# 1.net
KiCad netlist of a schematic drawn in EAGLE
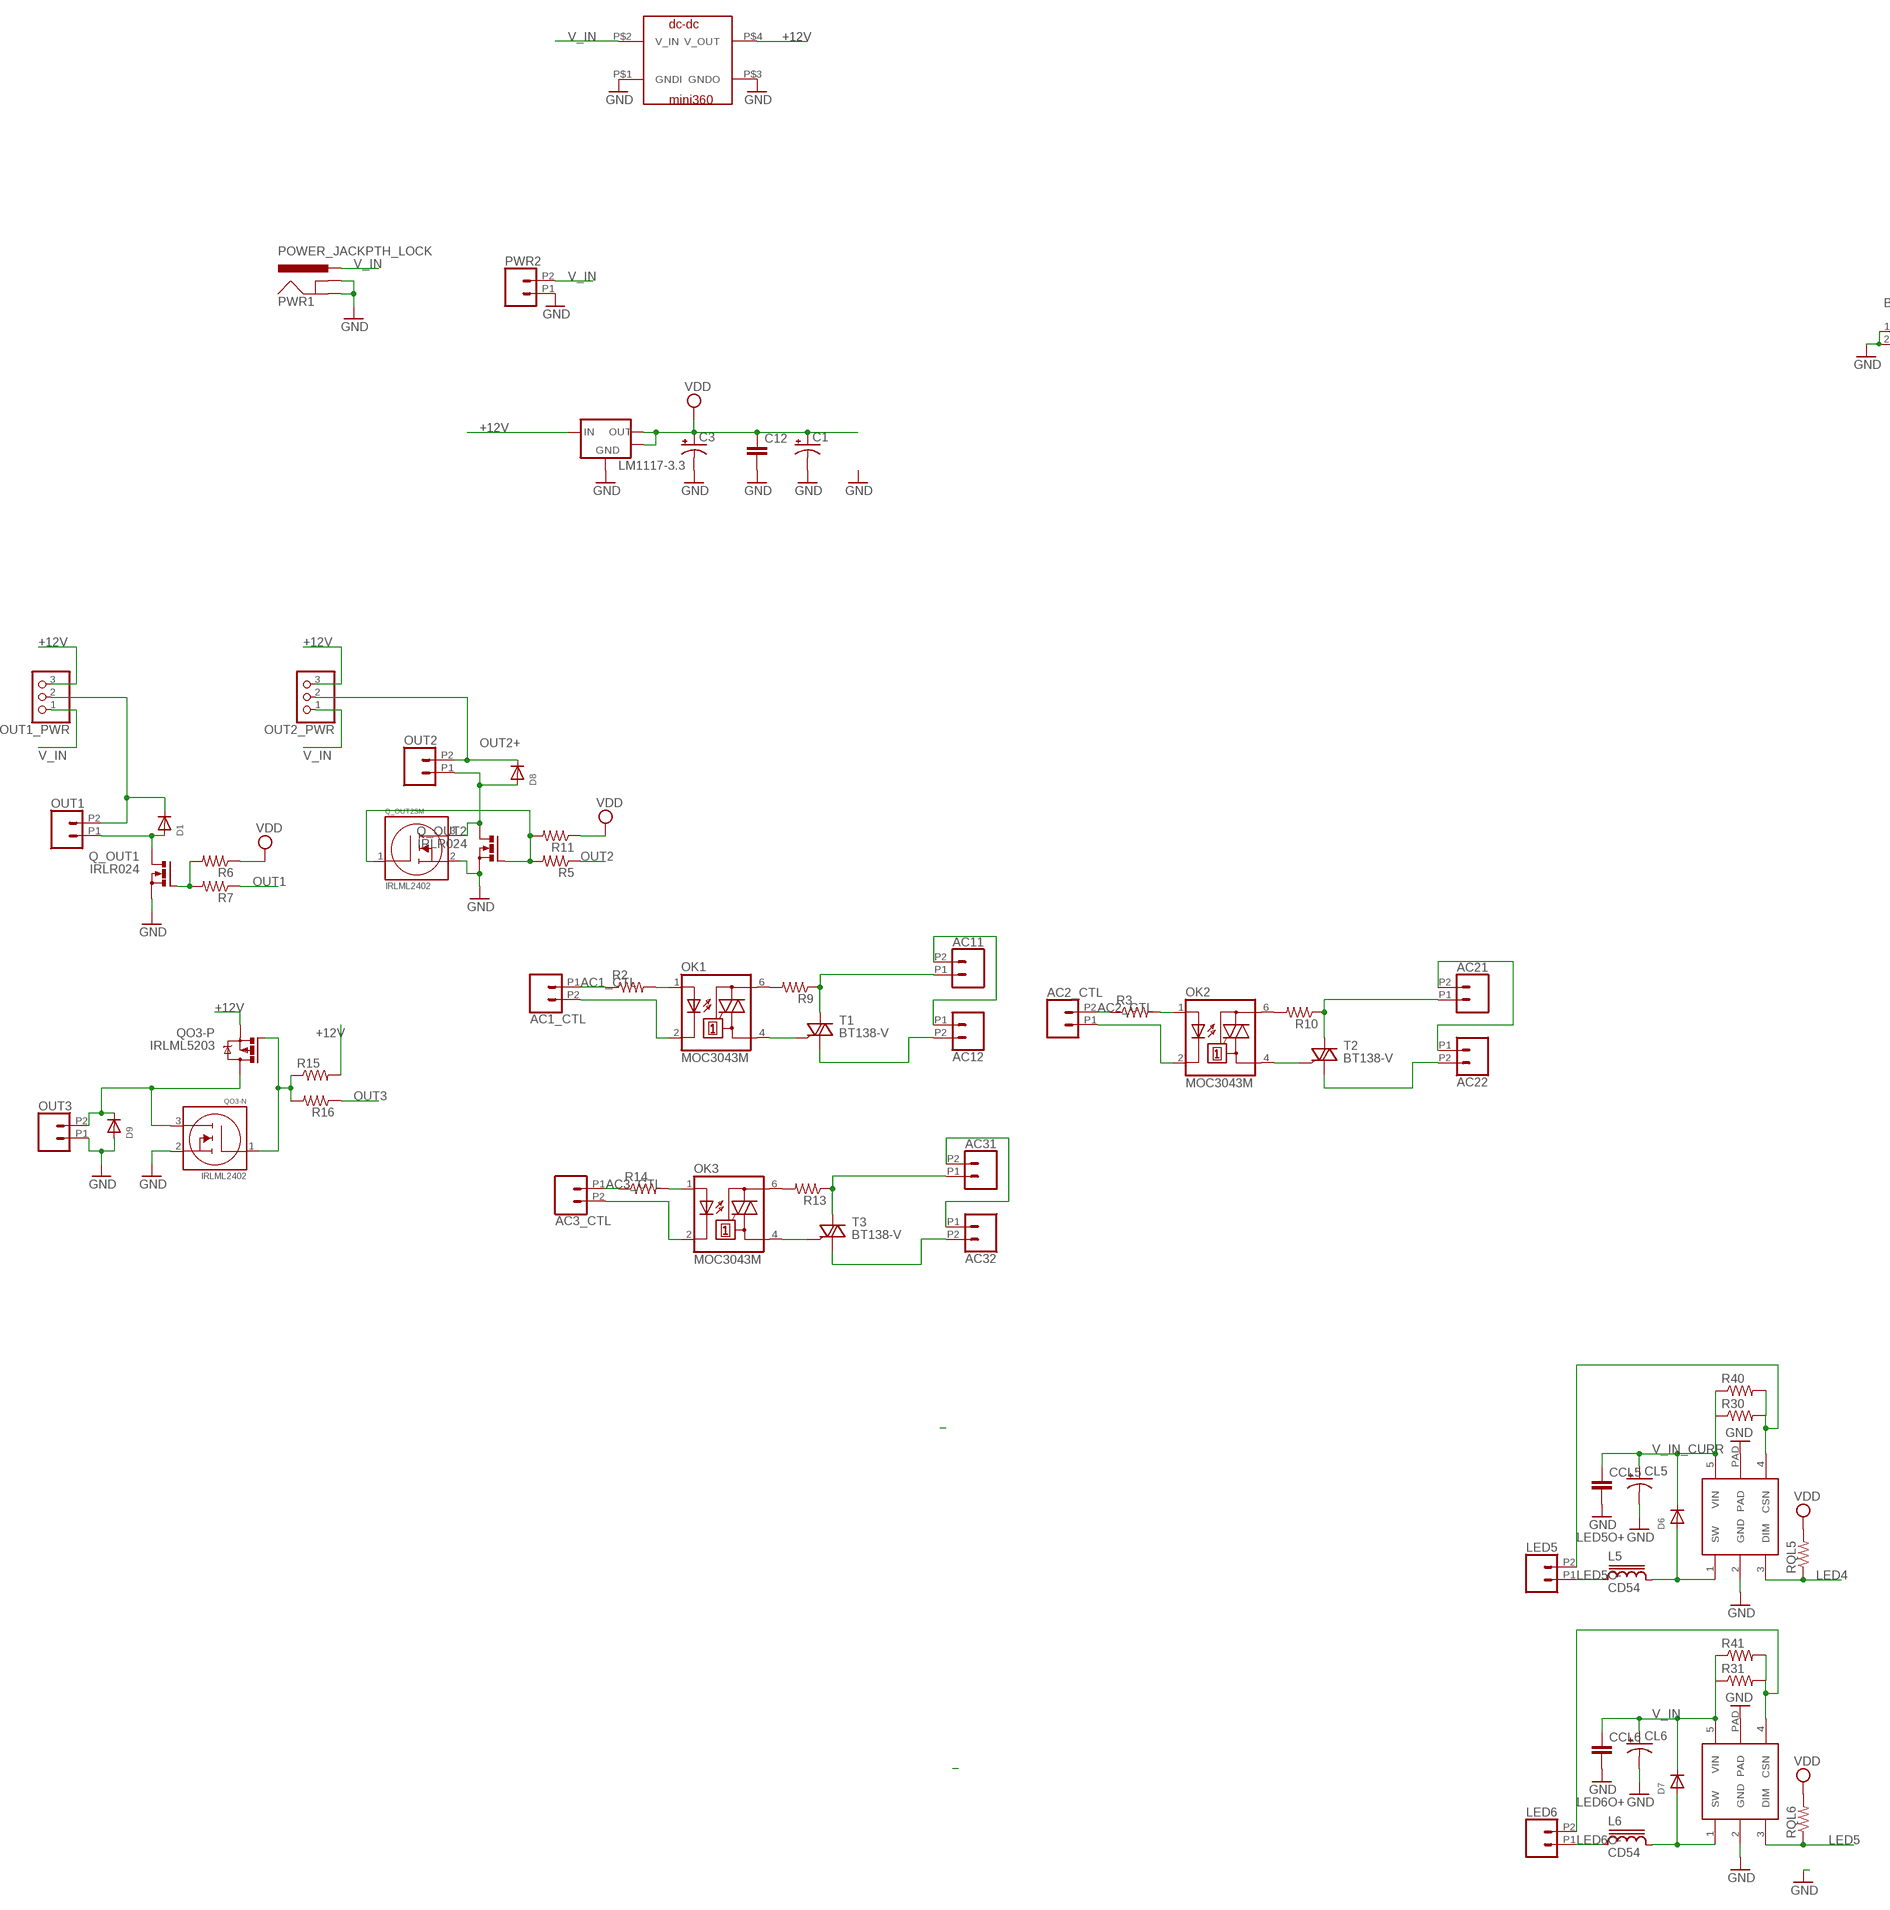
[diagram p0: schematic, sheet 1, part 1 of 3]
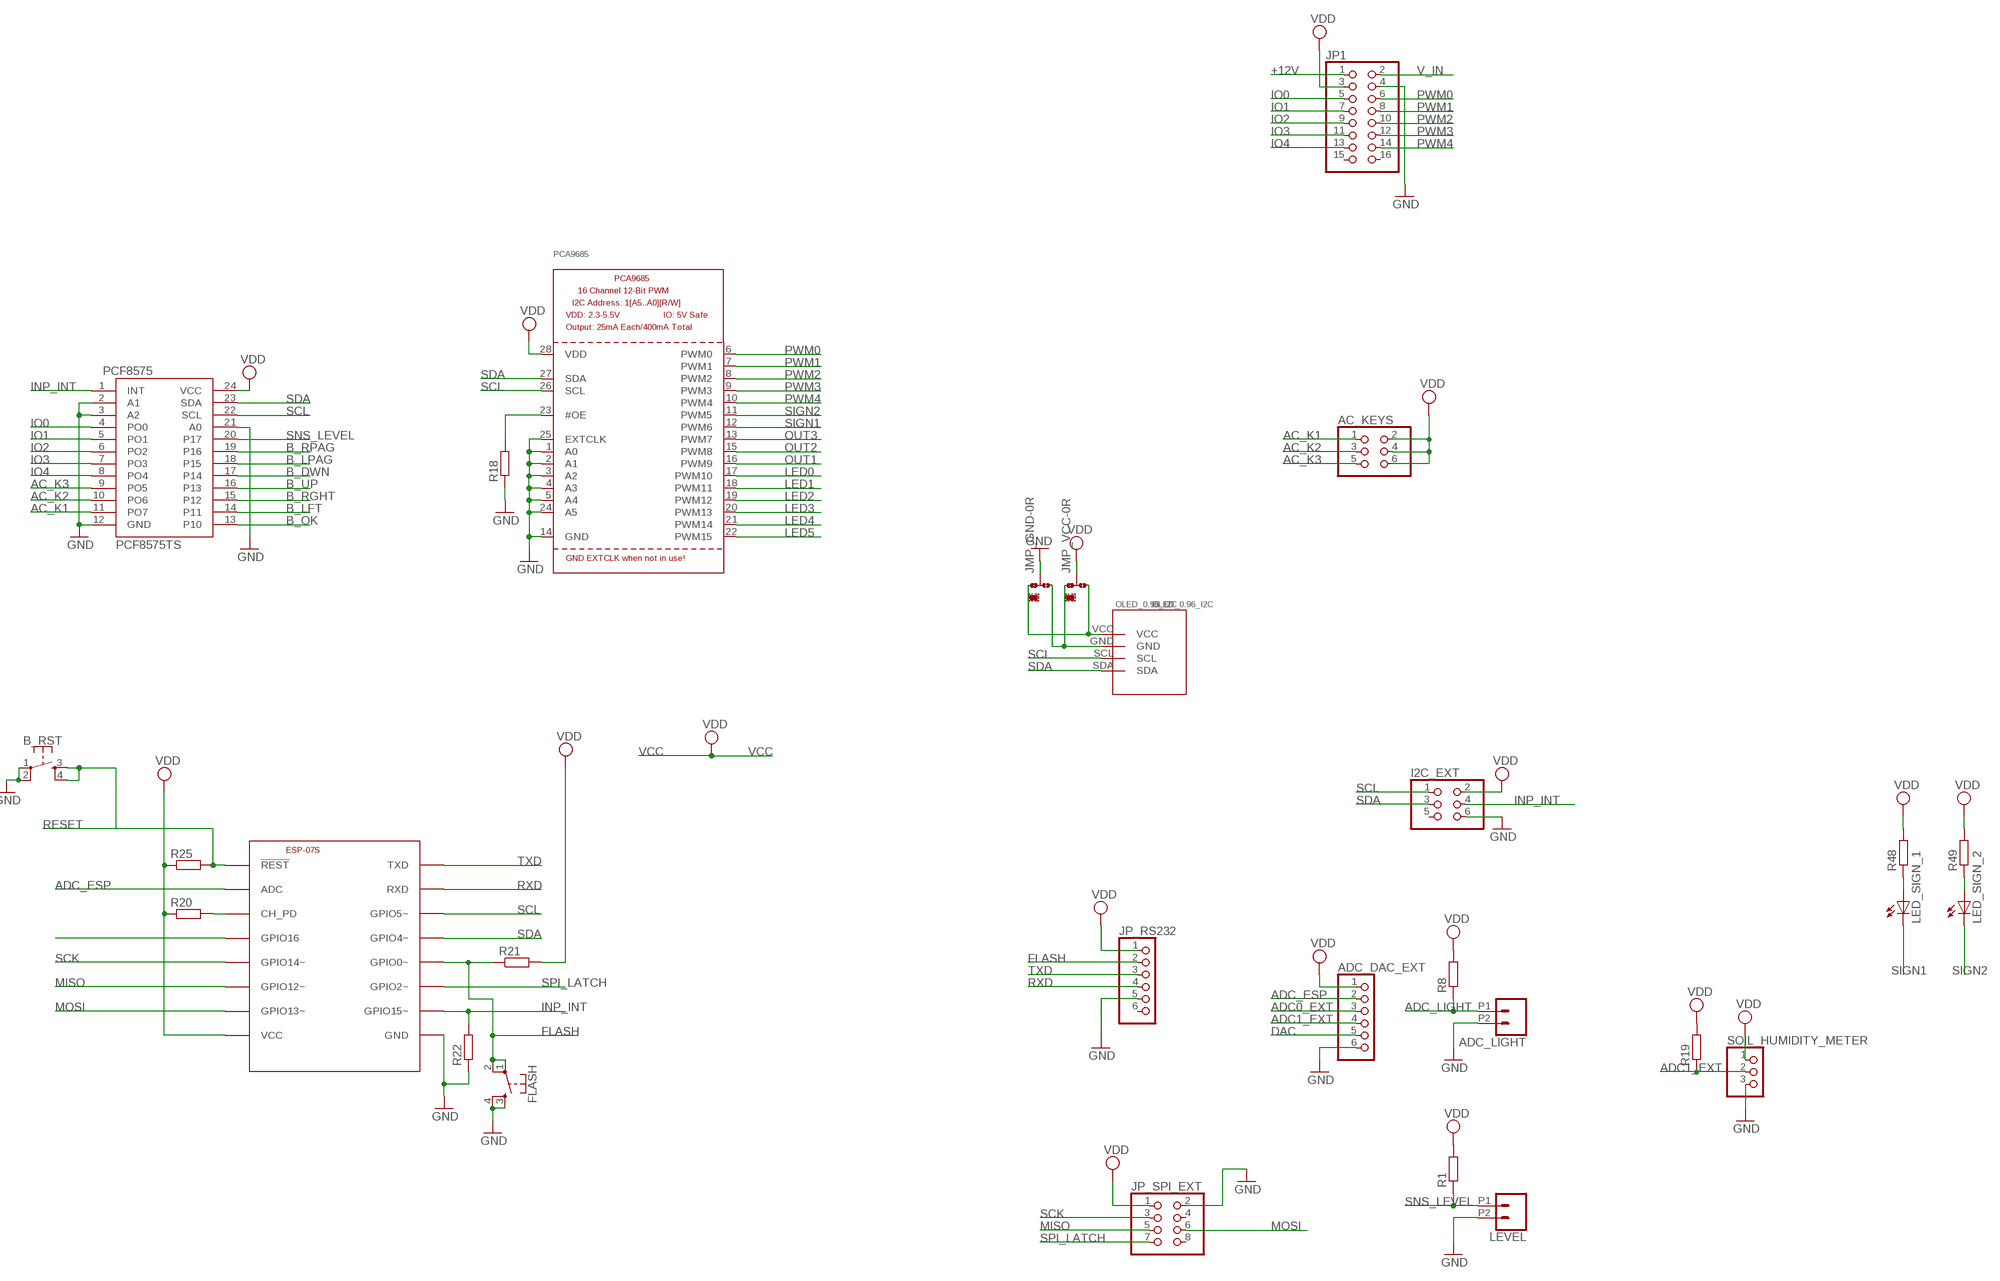
[diagram p1: schematic, sheet 1, part 2 of 3]
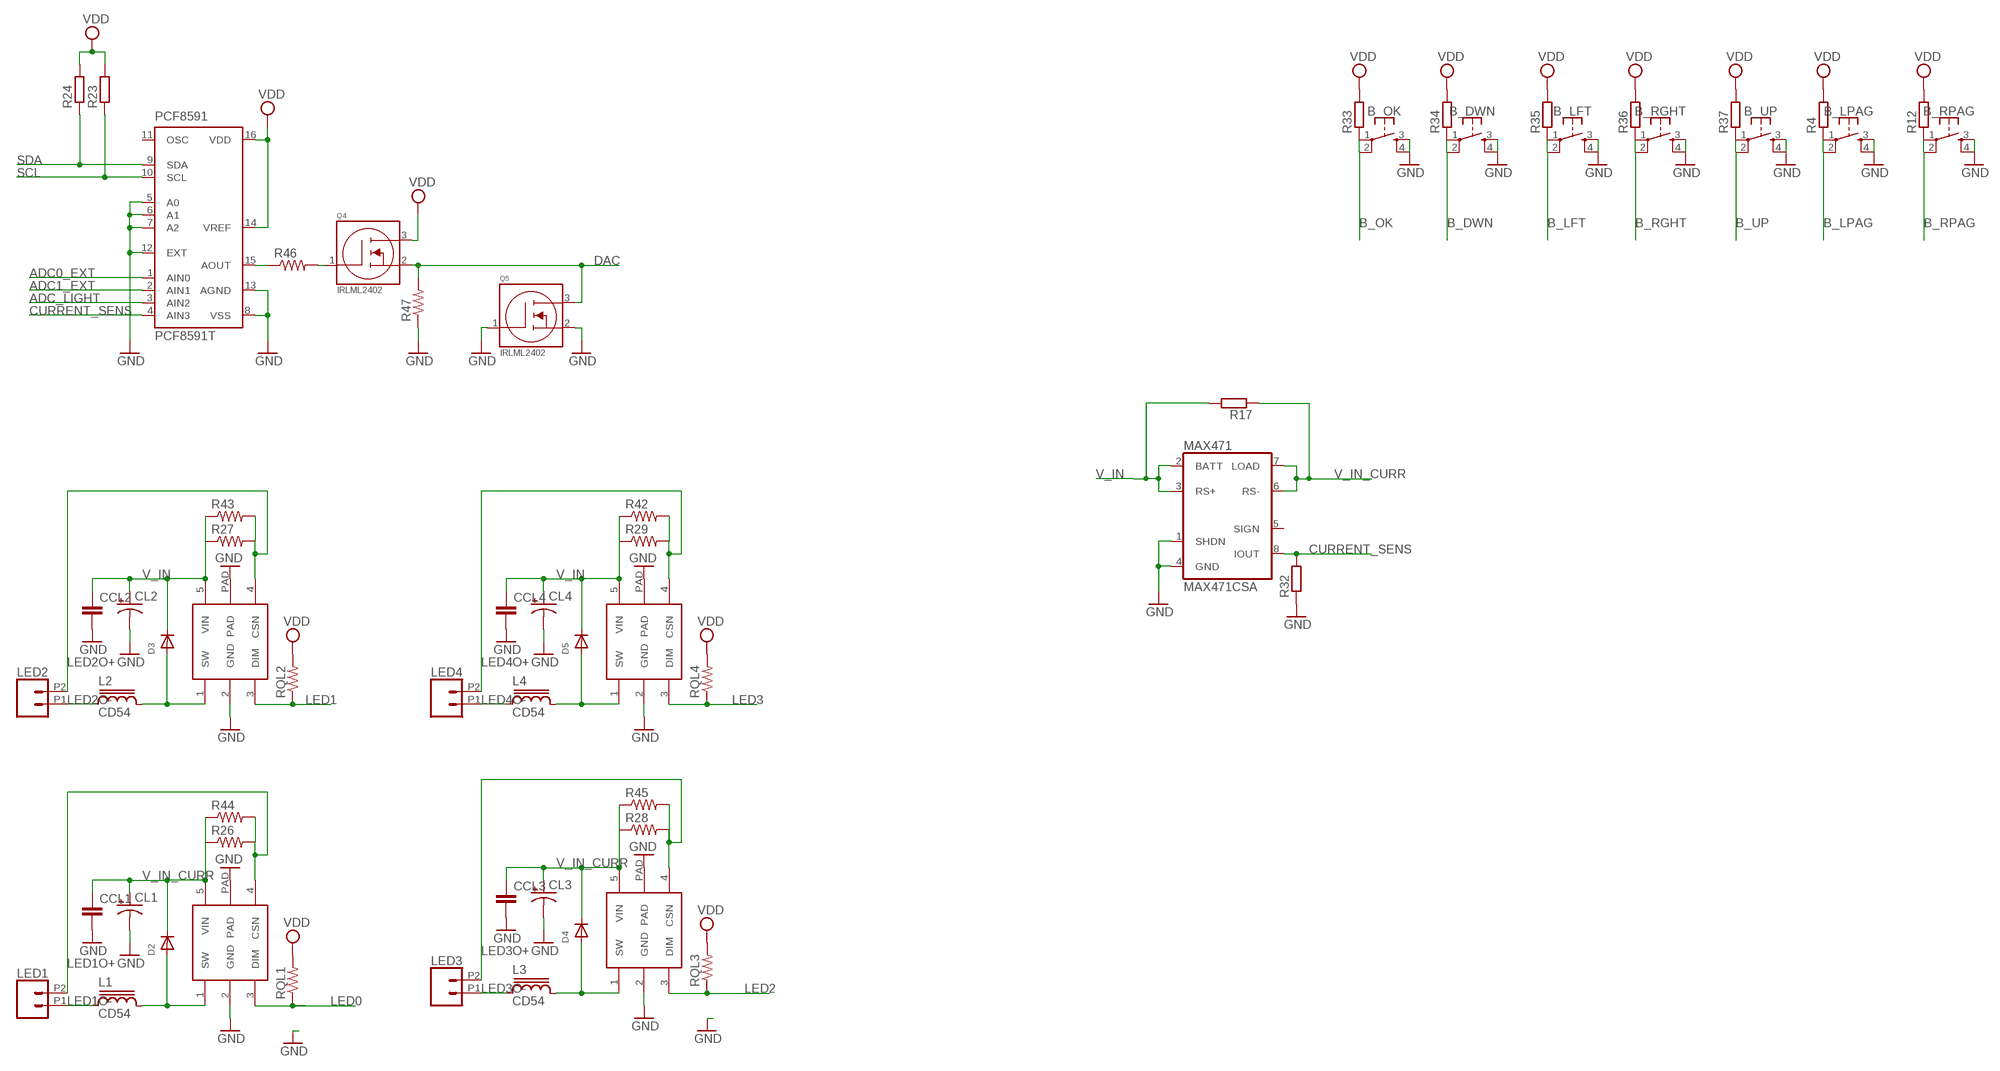
[diagram p2: schematic, sheet 1, part 3 of 3]

(export (version "E")
  (design (tool "Eeschema 10.0.6"))
  (components
    (comp (ref "AC1_CTL")
      (value "CONN_022.54MM_SCREWTERM")
      (footprint "eagle-import:1X02_2.54_SCREWTERM")
      (libsource (lib "eagle-import") (part "SparkFun-Retired_CONN_022.54MM_SCREWTERM"))
    )
    (comp (ref "AC2_CTL")
      (value "CONN_022.54MM_SCREWTERM")
      (footprint "eagle-import:1X02_2.54_SCREWTERM")
      (libsource (lib "eagle-import") (part "SparkFun-Retired_CONN_022.54MM_SCREWTERM"))
    )
    (comp (ref "AC3_CTL")
      (value "CONN_022.54MM_SCREWTERM")
      (footprint "eagle-import:1X02_2.54_SCREWTERM")
      (libsource (lib "eagle-import") (part "SparkFun-Retired_CONN_022.54MM_SCREWTERM"))
    )
    (comp (ref "AC11")
      (value "CONN_022.54MM_SCREWTERM")
      (footprint "eagle-import:1X02_2.54_SCREWTERM")
      (libsource (lib "eagle-import") (part "SparkFun-Retired_CONN_022.54MM_SCREWTERM"))
    )
    (comp (ref "AC12")
      (value "CONN_022.54MM_SCREWTERM")
      (footprint "eagle-import:1X02_2.54_SCREWTERM")
      (libsource (lib "eagle-import") (part "SparkFun-Retired_CONN_022.54MM_SCREWTERM"))
    )
    (comp (ref "AC21")
      (value "CONN_022.54MM_SCREWTERM")
      (footprint "eagle-import:1X02_2.54_SCREWTERM")
      (libsource (lib "eagle-import") (part "SparkFun-Retired_CONN_022.54MM_SCREWTERM"))
    )
    (comp (ref "AC22")
      (value "CONN_022.54MM_SCREWTERM")
      (footprint "eagle-import:1X02_2.54_SCREWTERM")
      (libsource (lib "eagle-import") (part "SparkFun-Retired_CONN_022.54MM_SCREWTERM"))
    )
    (comp (ref "AC31")
      (value "CONN_022.54MM_SCREWTERM")
      (footprint "eagle-import:1X02_2.54_SCREWTERM")
      (libsource (lib "eagle-import") (part "SparkFun-Retired_CONN_022.54MM_SCREWTERM"))
    )
    (comp (ref "AC32")
      (value "CONN_022.54MM_SCREWTERM")
      (footprint "eagle-import:1X02_2.54_SCREWTERM")
      (libsource (lib "eagle-import") (part "SparkFun-Retired_CONN_022.54MM_SCREWTERM"))
    )
    (comp (ref "AC_KEYS")
      (value "PINHD-2X3")
      (footprint "eagle-import:2X03")
      (libsource (lib "eagle-import") (part "PINHD-2X3"))
    )
    (comp (ref "ADC_DAC_EXT")
      (value "PINHD-1X6")
      (footprint "eagle-import:1X06")
      (libsource (lib "eagle-import") (part "PINHD-1X6"))
    )
    (comp (ref "ADC_LIGHT")
      (value "CONN_022.54MM_SCREWTERM")
      (footprint "eagle-import:1X02_2.54_SCREWTERM")
      (libsource (lib "eagle-import") (part "CONN_022.54MM_SCREWTERM"))
    )
    (comp (ref "B_DWN")
      (value "MOMENTARY-SWITCH-SPST-2-SMD-5.2MM")
      (footprint "eagle-import:TACTILE_SWITCH_SMD_5.2MM")
      (libsource (lib "eagle-import") (part "MOMENTARY-SWITCH-SPST-2-SMD-5.2MM"))
    )
    (comp (ref "B_LFT")
      (value "MOMENTARY-SWITCH-SPST-2-SMD-5.2MM")
      (footprint "eagle-import:TACTILE_SWITCH_SMD_5.2MM")
      (libsource (lib "eagle-import") (part "MOMENTARY-SWITCH-SPST-2-SMD-5.2MM"))
    )
    (comp (ref "B_LPAG")
      (value "MOMENTARY-SWITCH-SPST-2-SMD-5.2MM")
      (footprint "eagle-import:TACTILE_SWITCH_SMD_5.2MM")
      (libsource (lib "eagle-import") (part "MOMENTARY-SWITCH-SPST-2-SMD-5.2MM"))
    )
    (comp (ref "B_OK")
      (value "MOMENTARY-SWITCH-SPST-2-SMD-5.2MM")
      (footprint "eagle-import:TACTILE_SWITCH_SMD_5.2MM")
      (libsource (lib "eagle-import") (part "MOMENTARY-SWITCH-SPST-2-SMD-5.2MM"))
    )
    (comp (ref "B_RGHT")
      (value "MOMENTARY-SWITCH-SPST-2-SMD-5.2MM")
      (footprint "eagle-import:TACTILE_SWITCH_SMD_5.2MM")
      (libsource (lib "eagle-import") (part "MOMENTARY-SWITCH-SPST-2-SMD-5.2MM"))
    )
    (comp (ref "B_RPAG")
      (value "MOMENTARY-SWITCH-SPST-2-SMD-5.2MM")
      (footprint "eagle-import:TACTILE_SWITCH_SMD_5.2MM")
      (libsource (lib "eagle-import") (part "MOMENTARY-SWITCH-SPST-2-SMD-5.2MM"))
    )
    (comp (ref "B_RST")
      (value "MOMENTARY-SWITCH-SPST-2-SMD-5.2MM")
      (footprint "eagle-import:TACTILE_SWITCH_SMD_5.2MM")
      (libsource (lib "eagle-import") (part "MOMENTARY-SWITCH-SPST-2-SMD-5.2MM"))
    )
    (comp (ref "B_UP")
      (value "MOMENTARY-SWITCH-SPST-2-SMD-5.2MM")
      (footprint "eagle-import:TACTILE_SWITCH_SMD_5.2MM")
      (libsource (lib "eagle-import") (part "MOMENTARY-SWITCH-SPST-2-SMD-5.2MM"))
    )
    (comp (ref "C1")
      (value "CPOL-US153CLV-0505")
      (footprint "eagle-import:153CLV-0505")
      (libsource (lib "eagle-import") (part "CPOL-US153CLV-0505"))
    )
    (comp (ref "C3")
      (value "CPOL-US153CLV-0505")
      (footprint "eagle-import:153CLV-0505")
      (libsource (lib "eagle-import") (part "CPOL-US153CLV-0505"))
    )
    (comp (ref "C12")
      (value "C-EUC0805")
      (footprint "eagle-import:C0805")
      (libsource (lib "eagle-import") (part "C-EUC0805"))
    )
    (comp (ref "CCL1")
      (value "C-EUC0805K")
      (footprint "eagle-import:C0805K")
      (libsource (lib "eagle-import") (part "C-EUC0805K"))
    )
    (comp (ref "CCL2")
      (value "C-EUC0805K")
      (footprint "eagle-import:C0805K")
      (libsource (lib "eagle-import") (part "C-EUC0805K"))
    )
    (comp (ref "CCL3")
      (value "C-EUC0805K")
      (footprint "eagle-import:C0805K")
      (libsource (lib "eagle-import") (part "C-EUC0805K"))
    )
    (comp (ref "CCL4")
      (value "C-EUC0805K")
      (footprint "eagle-import:C0805K")
      (libsource (lib "eagle-import") (part "C-EUC0805K"))
    )
    (comp (ref "CCL5")
      (value "C-EUC0805K")
      (footprint "eagle-import:C0805K")
      (libsource (lib "eagle-import") (part "C-EUC0805K"))
    )
    (comp (ref "CCL6")
      (value "C-EUC0805K")
      (footprint "eagle-import:C0805K")
      (libsource (lib "eagle-import") (part "C-EUC0805K"))
    )
    (comp (ref "CL1")
      (value "CPOL-US153CLV-0605")
      (footprint "eagle-import:153CLV-0605")
      (libsource (lib "eagle-import") (part "CPOL-US153CLV-0605"))
    )
    (comp (ref "CL2")
      (value "CPOL-US153CLV-0605")
      (footprint "eagle-import:153CLV-0605")
      (libsource (lib "eagle-import") (part "CPOL-US153CLV-0605"))
    )
    (comp (ref "CL3")
      (value "CPOL-US153CLV-0605")
      (footprint "eagle-import:153CLV-0605")
      (libsource (lib "eagle-import") (part "CPOL-US153CLV-0605"))
    )
    (comp (ref "CL4")
      (value "CPOL-US153CLV-0605")
      (footprint "eagle-import:153CLV-0605")
      (libsource (lib "eagle-import") (part "CPOL-US153CLV-0605"))
    )
    (comp (ref "CL5")
      (value "CPOL-US153CLV-0605")
      (footprint "eagle-import:153CLV-0605")
      (libsource (lib "eagle-import") (part "CPOL-US153CLV-0605"))
    )
    (comp (ref "CL6")
      (value "CPOL-US153CLV-0605")
      (footprint "eagle-import:153CLV-0605")
      (libsource (lib "eagle-import") (part "CPOL-US153CLV-0605"))
    )
    (comp (ref "D1")
      (value "DIODESMA")
      (footprint "eagle-import:SMADIODE")
      (libsource (lib "eagle-import") (part "DIODESMA"))
    )
    (comp (ref "D2")
      (value "DIODESMA")
      (footprint "eagle-import:SMADIODE")
      (libsource (lib "eagle-import") (part "DIODESMA"))
    )
    (comp (ref "D3")
      (value "DIODESMA")
      (footprint "eagle-import:SMADIODE")
      (libsource (lib "eagle-import") (part "DIODESMA"))
    )
    (comp (ref "D4")
      (value "DIODESMA")
      (footprint "eagle-import:SMADIODE")
      (libsource (lib "eagle-import") (part "DIODESMA"))
    )
    (comp (ref "D5")
      (value "DIODESMA")
      (footprint "eagle-import:SMADIODE")
      (libsource (lib "eagle-import") (part "DIODESMA"))
    )
    (comp (ref "D6")
      (value "DIODESMA")
      (footprint "eagle-import:SMADIODE")
      (libsource (lib "eagle-import") (part "DIODESMA"))
    )
    (comp (ref "D7")
      (value "DIODESMA")
      (footprint "eagle-import:SMADIODE")
      (libsource (lib "eagle-import") (part "DIODESMA"))
    )
    (comp (ref "D8")
      (value "DIODESMA")
      (footprint "eagle-import:SMADIODE")
      (libsource (lib "eagle-import") (part "DIODESMA"))
    )
    (comp (ref "D9")
      (value "DIODESMA")
      (footprint "eagle-import:SMADIODE")
      (libsource (lib "eagle-import") (part "DIODESMA"))
    )
    (comp (ref "ESP-07S")
      (value "ESP8266-08")
      (footprint "eagle-import:ESP-08")
      (libsource (lib "eagle-import") (part "ESP8266-08"))
    )
    (comp (ref "FLASH")
      (value "MOMENTARY-SWITCH-SPST-2-SMD-5.2MM")
      (footprint "eagle-import:TACTILE_SWITCH_SMD_5.2MM")
      (libsource (lib "eagle-import") (part "MOMENTARY-SWITCH-SPST-2-SMD-5.2MM"))
    )
    (comp (ref "I2C_EXT")
      (value "PINHD-2X3")
      (footprint "eagle-import:2X03")
      (libsource (lib "eagle-import") (part "PINHD-2X3"))
    )
    (comp (ref "JMP_GND")
      (value "0R-JUMPA")
      (footprint "eagle-import:A0R-JMP")
      (libsource (lib "eagle-import") (part "0R-JUMPA"))
    )
    (comp (ref "JMP_VCC")
      (value "0R-JUMPA")
      (footprint "eagle-import:A0R-JMP")
      (libsource (lib "eagle-import") (part "0R-JUMPA"))
    )
    (comp (ref "JP1")
      (value "PINHD-2X8")
      (footprint "eagle-import:2X08")
      (libsource (lib "eagle-import") (part "PINHD-2X8"))
    )
    (comp (ref "JP_RS232")
      (value "PINHD-1X6")
      (footprint "eagle-import:1X06")
      (libsource (lib "eagle-import") (part "PINHD-1X6"))
    )
    (comp (ref "JP_SPI_EXT")
      (value "PINHD-2X4")
      (footprint "eagle-import:2X04")
      (libsource (lib "eagle-import") (part "PINHD-2X4"))
    )
    (comp (ref "L1")
      (value "CD54")
      (footprint "eagle-import:CD54")
      (libsource (lib "eagle-import") (part "CD54"))
    )
    (comp (ref "L2")
      (value "CD54")
      (footprint "eagle-import:CD54")
      (libsource (lib "eagle-import") (part "CD54"))
    )
    (comp (ref "L3")
      (value "CD54")
      (footprint "eagle-import:CD54")
      (libsource (lib "eagle-import") (part "CD54"))
    )
    (comp (ref "L4")
      (value "CD54")
      (footprint "eagle-import:CD54")
      (libsource (lib "eagle-import") (part "CD54"))
    )
    (comp (ref "L5")
      (value "CD54")
      (footprint "eagle-import:CD54")
      (libsource (lib "eagle-import") (part "CD54"))
    )
    (comp (ref "L6")
      (value "CD54")
      (footprint "eagle-import:CD54")
      (libsource (lib "eagle-import") (part "CD54"))
    )
    (comp (ref "LED1")
      (value "CONN_022.54MM_SCREWTERM")
      (footprint "eagle-import:1X02_2.54_SCREWTERM")
      (libsource (lib "eagle-import") (part "CONN_022.54MM_SCREWTERM"))
    )
    (comp (ref "LED2")
      (value "CONN_022.54MM_SCREWTERM")
      (footprint "eagle-import:1X02_2.54_SCREWTERM")
      (libsource (lib "eagle-import") (part "CONN_022.54MM_SCREWTERM"))
    )
    (comp (ref "LED3")
      (value "CONN_022.54MM_SCREWTERM")
      (footprint "eagle-import:1X02_2.54_SCREWTERM")
      (libsource (lib "eagle-import") (part "CONN_022.54MM_SCREWTERM"))
    )
    (comp (ref "LED4")
      (value "CONN_022.54MM_SCREWTERM")
      (footprint "eagle-import:1X02_2.54_SCREWTERM")
      (libsource (lib "eagle-import") (part "CONN_022.54MM_SCREWTERM"))
    )
    (comp (ref "LED5")
      (value "CONN_022.54MM_SCREWTERM")
      (footprint "eagle-import:1X02_2.54_SCREWTERM")
      (libsource (lib "eagle-import") (part "CONN_022.54MM_SCREWTERM"))
    )
    (comp (ref "LED6")
      (value "CONN_022.54MM_SCREWTERM")
      (footprint "eagle-import:1X02_2.54_SCREWTERM")
      (libsource (lib "eagle-import") (part "CONN_022.54MM_SCREWTERM"))
    )
    (comp (ref "LED_SIGN_1")
      (value "LEDCHIP-LED0805")
      (footprint "eagle-import:CHIP-LED0805")
      (libsource (lib "eagle-import") (part "LEDCHIP-LED0805"))
    )
    (comp (ref "LED_SIGN_2")
      (value "LEDCHIP-LED0805")
      (footprint "eagle-import:CHIP-LED0805")
      (libsource (lib "eagle-import") (part "LEDCHIP-LED0805"))
    )
    (comp (ref "LEVEL")
      (value "CONN_022.54MM_SCREWTERM")
      (footprint "eagle-import:1X02_2.54_SCREWTERM")
      (libsource (lib "eagle-import") (part "CONN_022.54MM_SCREWTERM"))
    )
    (comp (ref "LM1117-3.3")
      (value "LM1117-3.3")
      (footprint "eagle-import:SOT223")
      (libsource (lib "eagle-import") (part "LM1117-3.3"))
    )
    (comp (ref "MAX471")
      (value "MAX471CSA")
      (footprint "eagle-import:SO08")
      (libsource (lib "eagle-import") (part "MAX471CSA"))
    )
    (comp (ref "OK1")
      (value "MOC3043M")
      (footprint "eagle-import:DIL06")
      (fields (field (name "MF") "FAIRCHILD SEMICONDUCTOR") (field (name "MPN") "MOC3043-M"))
      (libsource (lib "eagle-import") (part "MOC3043M"))
    )
    (comp (ref "OK2")
      (value "MOC3043M")
      (footprint "eagle-import:DIL06")
      (fields (field (name "MF") "FAIRCHILD SEMICONDUCTOR") (field (name "MPN") "MOC3043-M"))
      (libsource (lib "eagle-import") (part "MOC3043M"))
    )
    (comp (ref "OK3")
      (value "MOC3043M")
      (footprint "eagle-import:DIL06")
      (fields (field (name "MF") "FAIRCHILD SEMICONDUCTOR") (field (name "MPN") "MOC3043-M"))
      (libsource (lib "eagle-import") (part "MOC3043M"))
    )
    (comp (ref "OLED_0.96_I2C")
      (value "OLED_0.96_I2C")
      (footprint "eagle-import:OLED_0.96_I2C")
      (libsource (lib "eagle-import") (part "OLED_0.96_I2C"))
    )
    (comp (ref "OUT1")
      (value "CONN_022.54MM_SCREWTERM")
      (footprint "eagle-import:1X02_2.54_SCREWTERM")
      (libsource (lib "eagle-import") (part "CONN_022.54MM_SCREWTERM"))
    )
    (comp (ref "OUT1_PWR")
      (value "PINHD-1X3")
      (footprint "eagle-import:1X03")
      (libsource (lib "eagle-import") (part "PINHD-1X3"))
    )
    (comp (ref "OUT2")
      (value "CONN_022.54MM_SCREWTERM")
      (footprint "eagle-import:1X02_2.54_SCREWTERM")
      (libsource (lib "eagle-import") (part "CONN_022.54MM_SCREWTERM"))
    )
    (comp (ref "OUT2_PWR")
      (value "PINHD-1X3")
      (footprint "eagle-import:1X03")
      (libsource (lib "eagle-import") (part "PINHD-1X3"))
    )
    (comp (ref "OUT3")
      (value "CONN_022.54MM_SCREWTERM")
      (footprint "eagle-import:1X02_2.54_SCREWTERM")
      (libsource (lib "eagle-import") (part "CONN_022.54MM_SCREWTERM"))
    )
    (comp (ref "PCA9685")
      (value "PCA9685")
      (footprint "eagle-import:TSSOP28")
      (libsource (lib "eagle-import") (part "PCA9685"))
    )
    (comp (ref "PCF8575")
      (value "PCF8575TS")
      (footprint "eagle-import:SSOP24")
      (libsource (lib "eagle-import") (part "PCF8575TS"))
    )
    (comp (ref "PCF8591")
      (value "PCF8591T")
      (footprint "eagle-import:SO16W")
      (fields (field (name "MPN") "PCF8591T/2,512"))
      (libsource (lib "eagle-import") (part "PCF8591T"))
    )
    (comp (ref "PWR1")
      (value "POWER_JACKPTH_LOCK")
      (footprint "eagle-import:POWER_JACK_PTH_LOCK")
      (libsource (lib "eagle-import") (part "POWER_JACKPTH_LOCK"))
    )
    (comp (ref "PWR2")
      (value "CONN_022.54MM_SCREWTERM")
      (footprint "eagle-import:1X02_2.54_SCREWTERM")
      (libsource (lib "eagle-import") (part "CONN_022.54MM_SCREWTERM"))
    )
    (comp (ref "Q4")
      (value "IRLML2402")
      (footprint "eagle-import:SOT23")
      (libsource (lib "eagle-import") (part "IRLML2402"))
    )
    (comp (ref "Q5")
      (value "IRLML2402")
      (footprint "eagle-import:SOT23")
      (libsource (lib "eagle-import") (part "IRLML2402"))
    )
    (comp (ref "QO3-N")
      (value "IRLML2402")
      (footprint "eagle-import:SOT23")
      (libsource (lib "eagle-import") (part "IRLML2402"))
    )
    (comp (ref "QO3-P")
      (value "IRLML5203")
      (footprint "eagle-import:MICRO3")
      (libsource (lib "eagle-import") (part "IRLML5203"))
    )
    (comp (ref "Q_OUT1")
      (value "IRLR024")
      (footprint "eagle-import:D-PAK_TO252AA")
      (libsource (lib "eagle-import") (part "IRLR024"))
    )
    (comp (ref "Q_OUT2")
      (value "IRLR024")
      (footprint "eagle-import:D-PAK_TO252AA")
      (libsource (lib "eagle-import") (part "IRLR024"))
    )
    (comp (ref "Q_OUT2SM")
      (value "IRLML2402")
      (footprint "eagle-import:SOT23")
      (libsource (lib "eagle-import") (part "IRLML2402"))
    )
    (comp (ref "R1")
      (value "R-EU_M0805")
      (footprint "eagle-import:M0805")
      (libsource (lib "eagle-import") (part "R-EU_M0805"))
    )
    (comp (ref "R2")
      (value "RESISTOR0805-RES")
      (footprint "eagle-import:0805")
      (libsource (lib "eagle-import") (part "RESISTOR0805-RES"))
    )
    (comp (ref "R3")
      (value "RESISTOR0805-RES")
      (footprint "eagle-import:0805")
      (libsource (lib "eagle-import") (part "RESISTOR0805-RES"))
    )
    (comp (ref "R4")
      (value "R-EU_M0805")
      (footprint "eagle-import:M0805")
      (libsource (lib "eagle-import") (part "R-EU_M0805"))
    )
    (comp (ref "R5")
      (value "RESISTOR0805-RES")
      (footprint "eagle-import:0805")
      (libsource (lib "eagle-import") (part "RESISTOR0805-RES"))
    )
    (comp (ref "R6")
      (value "RESISTOR0805-RES")
      (footprint "eagle-import:0805")
      (libsource (lib "eagle-import") (part "RESISTOR0805-RES"))
    )
    (comp (ref "R7")
      (value "RESISTOR0805-RES")
      (footprint "eagle-import:0805")
      (libsource (lib "eagle-import") (part "RESISTOR0805-RES"))
    )
    (comp (ref "R8")
      (value "R-EU_M0805")
      (footprint "eagle-import:M0805")
      (libsource (lib "eagle-import") (part "R-EU_M0805"))
    )
    (comp (ref "R9")
      (value "RESISTOR0805-RES")
      (footprint "eagle-import:0805")
      (libsource (lib "eagle-import") (part "RESISTOR0805-RES"))
    )
    (comp (ref "R10")
      (value "RESISTOR0805-RES")
      (footprint "eagle-import:0805")
      (libsource (lib "eagle-import") (part "RESISTOR0805-RES"))
    )
    (comp (ref "R11")
      (value "RESISTOR0805-RES")
      (footprint "eagle-import:0805")
      (libsource (lib "eagle-import") (part "RESISTOR0805-RES"))
    )
    (comp (ref "R12")
      (value "R-EU_M0805")
      (footprint "eagle-import:M0805")
      (libsource (lib "eagle-import") (part "R-EU_M0805"))
    )
    (comp (ref "R13")
      (value "RESISTOR0805-RES")
      (footprint "eagle-import:0805")
      (libsource (lib "eagle-import") (part "RESISTOR0805-RES"))
    )
    (comp (ref "R14")
      (value "RESISTOR0805-RES")
      (footprint "eagle-import:0805")
      (libsource (lib "eagle-import") (part "RESISTOR0805-RES"))
    )
    (comp (ref "R15")
      (value "RESISTOR0805-RES")
      (footprint "eagle-import:0805")
      (libsource (lib "eagle-import") (part "RESISTOR0805-RES"))
    )
    (comp (ref "R16")
      (value "RESISTOR0805-RES")
      (footprint "eagle-import:0805")
      (libsource (lib "eagle-import") (part "RESISTOR0805-RES"))
    )
    (comp (ref "R17")
      (value "R-EU_M0805")
      (footprint "eagle-import:M0805")
      (libsource (lib "eagle-import") (part "R-EU_M0805"))
    )
    (comp (ref "R18")
      (value "R-EU_M0805")
      (footprint "eagle-import:M0805")
      (libsource (lib "eagle-import") (part "R-EU_M0805"))
    )
    (comp (ref "R19")
      (value "R-EU_M0805")
      (footprint "eagle-import:M0805")
      (libsource (lib "eagle-import") (part "R-EU_M0805"))
    )
    (comp (ref "R20")
      (value "R-EU_M0805")
      (footprint "eagle-import:M0805")
      (libsource (lib "eagle-import") (part "R-EU_M0805"))
    )
    (comp (ref "R21")
      (value "R-EU_M0805")
      (footprint "eagle-import:M0805")
      (libsource (lib "eagle-import") (part "R-EU_M0805"))
    )
    (comp (ref "R22")
      (value "R-EU_M0805")
      (footprint "eagle-import:M0805")
      (libsource (lib "eagle-import") (part "R-EU_M0805"))
    )
    (comp (ref "R23")
      (value "R-EU_M0805")
      (footprint "eagle-import:M0805")
      (libsource (lib "eagle-import") (part "R-EU_M0805"))
    )
    (comp (ref "R24")
      (value "R-EU_M0805")
      (footprint "eagle-import:M0805")
      (libsource (lib "eagle-import") (part "R-EU_M0805"))
    )
    (comp (ref "R25")
      (value "R-EU_M0805")
      (footprint "eagle-import:M0805")
      (libsource (lib "eagle-import") (part "R-EU_M0805"))
    )
    (comp (ref "R26")
      (value "RESISTOR")
      (footprint "eagle-import:0805")
      (libsource (lib "eagle-import") (part "RESISTOR"))
    )
    (comp (ref "R27")
      (value "RESISTOR")
      (footprint "eagle-import:0805")
      (libsource (lib "eagle-import") (part "RESISTOR"))
    )
    (comp (ref "R28")
      (value "RESISTOR")
      (footprint "eagle-import:0805")
      (libsource (lib "eagle-import") (part "RESISTOR"))
    )
    (comp (ref "R29")
      (value "RESISTOR")
      (footprint "eagle-import:0805")
      (libsource (lib "eagle-import") (part "RESISTOR"))
    )
    (comp (ref "R30")
      (value "RESISTOR")
      (footprint "eagle-import:0805")
      (libsource (lib "eagle-import") (part "RESISTOR"))
    )
    (comp (ref "R31")
      (value "RESISTOR")
      (footprint "eagle-import:0805")
      (libsource (lib "eagle-import") (part "RESISTOR"))
    )
    (comp (ref "R32")
      (value "R-EU_M0805")
      (footprint "eagle-import:M0805")
      (libsource (lib "eagle-import") (part "R-EU_M0805"))
    )
    (comp (ref "R33")
      (value "R-EU_M0805")
      (footprint "eagle-import:M0805")
      (libsource (lib "eagle-import") (part "R-EU_M0805"))
    )
    (comp (ref "R34")
      (value "R-EU_M0805")
      (footprint "eagle-import:M0805")
      (libsource (lib "eagle-import") (part "R-EU_M0805"))
    )
    (comp (ref "R35")
      (value "R-EU_M0805")
      (footprint "eagle-import:M0805")
      (libsource (lib "eagle-import") (part "R-EU_M0805"))
    )
    (comp (ref "R36")
      (value "R-EU_M0805")
      (footprint "eagle-import:M0805")
      (libsource (lib "eagle-import") (part "R-EU_M0805"))
    )
    (comp (ref "R37")
      (value "R-EU_M0805")
      (footprint "eagle-import:M0805")
      (libsource (lib "eagle-import") (part "R-EU_M0805"))
    )
    (comp (ref "R40")
      (value "RESISTOR")
      (footprint "eagle-import:0805")
      (libsource (lib "eagle-import") (part "RESISTOR"))
    )
    (comp (ref "R41")
      (value "RESISTOR")
      (footprint "eagle-import:0805")
      (libsource (lib "eagle-import") (part "RESISTOR"))
    )
    (comp (ref "R42")
      (value "RESISTOR")
      (footprint "eagle-import:0805")
      (libsource (lib "eagle-import") (part "RESISTOR"))
    )
    (comp (ref "R43")
      (value "RESISTOR")
      (footprint "eagle-import:0805")
      (libsource (lib "eagle-import") (part "RESISTOR"))
    )
    (comp (ref "R44")
      (value "RESISTOR")
      (footprint "eagle-import:0805")
      (libsource (lib "eagle-import") (part "RESISTOR"))
    )
    (comp (ref "R45")
      (value "RESISTOR")
      (footprint "eagle-import:0805")
      (libsource (lib "eagle-import") (part "RESISTOR"))
    )
    (comp (ref "R46")
      (value "RESISTOR")
      (footprint "eagle-import:0805")
      (libsource (lib "eagle-import") (part "RESISTOR"))
    )
    (comp (ref "R47")
      (value "RESISTOR")
      (footprint "eagle-import:0805")
      (libsource (lib "eagle-import") (part "RESISTOR"))
    )
    (comp (ref "R48")
      (value "R-EU_M0805")
      (footprint "eagle-import:M0805")
      (libsource (lib "eagle-import") (part "R-EU_M0805"))
    )
    (comp (ref "R49")
      (value "R-EU_M0805")
      (footprint "eagle-import:M0805")
      (libsource (lib "eagle-import") (part "R-EU_M0805"))
    )
    (comp (ref "RQL1")
      (value "RESISTOR")
      (footprint "eagle-import:0805")
      (libsource (lib "eagle-import") (part "RESISTOR"))
    )
    (comp (ref "RQL2")
      (value "RESISTOR")
      (footprint "eagle-import:0805")
      (libsource (lib "eagle-import") (part "RESISTOR"))
    )
    (comp (ref "RQL3")
      (value "RESISTOR")
      (footprint "eagle-import:0805")
      (libsource (lib "eagle-import") (part "RESISTOR"))
    )
    (comp (ref "RQL4")
      (value "RESISTOR")
      (footprint "eagle-import:0805")
      (libsource (lib "eagle-import") (part "RESISTOR"))
    )
    (comp (ref "RQL5")
      (value "RESISTOR")
      (footprint "eagle-import:0805")
      (libsource (lib "eagle-import") (part "RESISTOR"))
    )
    (comp (ref "RQL6")
      (value "RESISTOR")
      (footprint "eagle-import:0805")
      (libsource (lib "eagle-import") (part "RESISTOR"))
    )
    (comp (ref "SOIL_HUMIDITY_METER")
      (value "PINHD-1X3")
      (footprint "eagle-import:1X03")
      (libsource (lib "eagle-import") (part "PINHD-1X3"))
    )
    (comp (ref "T1")
      (value "BT138-V")
      (footprint "eagle-import:TO220BV")
      (libsource (lib "eagle-import") (part "BT138-V"))
    )
    (comp (ref "T2")
      (value "BT138-V")
      (footprint "eagle-import:TO220BV")
      (libsource (lib "eagle-import") (part "BT138-V"))
    )
    (comp (ref "T3")
      (value "BT138-V")
      (footprint "eagle-import:TO220BV")
      (libsource (lib "eagle-import") (part "BT138-V"))
    )
    (comp (ref "U$6")
      (value "PT4115")
      (footprint "eagle-import:SOT89-5")
      (libsource (lib "eagle-import") (part "PT4115"))
    )
    (comp (ref "U$7")
      (value "PT4115")
      (footprint "eagle-import:SOT89-5")
      (libsource (lib "eagle-import") (part "PT4115"))
    )
    (comp (ref "U$8")
      (value "PT4115")
      (footprint "eagle-import:SOT89-5")
      (libsource (lib "eagle-import") (part "PT4115"))
    )
    (comp (ref "U$9")
      (value "PT4115")
      (footprint "eagle-import:SOT89-5")
      (libsource (lib "eagle-import") (part "PT4115"))
    )
    (comp (ref "U$10")
      (value "PT4115")
      (footprint "eagle-import:SOT89-5")
      (libsource (lib "eagle-import") (part "PT4115"))
    )
    (comp (ref "U$12")
      (value "MINI360")
      (footprint "eagle-import:MINI360")
      (libsource (lib "eagle-import") (part "MINI360"))
    )
    (comp (ref "U$13")
      (value "PT4115")
      (footprint "eagle-import:SOT89-5")
      (libsource (lib "eagle-import") (part "PT4115"))
    )
  )
  (nets
    (net (code "1") (name "/+12V") (class "Default")
      (node (ref "JP1") (pin "1") (pinfunction "1_1") (pintype "passive"))
      (node (ref "LM1117-3.3") (pin "3") (pinfunction "IN_3") (pintype "power_in"))
      (node (ref "OUT1_PWR") (pin "3") (pinfunction "3_3") (pintype "passive"))
      (node (ref "OUT2_PWR") (pin "3") (pinfunction "3_3") (pintype "passive"))
      (node (ref "QO3-P") (pin "2") (pinfunction "S_2") (pintype "passive"))
      (node (ref "R15") (pin "2") (pinfunction "2_2") (pintype "passive"))
      (node (ref "U$12") (pin "P$4") (pinfunction "V_OUT_P$4") (pintype "bidirectional"))
    )
    (net (code "2") (name "/AC1_CTL") (class "Default")
      (node (ref "AC1_CTL") (pin "P1") (pinfunction "1_P1") (pintype "passive"))
      (node (ref "R2") (pin "1") (pinfunction "1_1") (pintype "passive"))
    )
    (net (code "3") (name "/AC2_CTL") (class "Default")
      (node (ref "AC2_CTL") (pin "P2") (pinfunction "2_P2") (pintype "passive"))
      (node (ref "R3") (pin "1") (pinfunction "1_1") (pintype "passive"))
    )
    (net (code "4") (name "/AC3_CTL") (class "Default")
      (node (ref "AC3_CTL") (pin "P1") (pinfunction "1_P1") (pintype "passive"))
      (node (ref "R14") (pin "1") (pinfunction "1_1") (pintype "passive"))
    )
    (net (code "5") (name "/AC_K1") (class "Default")
      (node (ref "AC_KEYS") (pin "1") (pinfunction "1_1") (pintype "passive"))
      (node (ref "PCF8575") (pin "11") (pinfunction "PO7_11") (pintype "bidirectional"))
    )
    (net (code "6") (name "/AC_K2") (class "Default")
      (node (ref "AC_KEYS") (pin "3") (pinfunction "3_3") (pintype "passive"))
      (node (ref "PCF8575") (pin "10") (pinfunction "PO6_10") (pintype "bidirectional"))
    )
    (net (code "7") (name "/AC_K3") (class "Default")
      (node (ref "AC_KEYS") (pin "5") (pinfunction "5_5") (pintype "passive"))
      (node (ref "PCF8575") (pin "9") (pinfunction "PO5_9") (pintype "bidirectional"))
    )
    (net (code "8") (name "/ADC0_EXT") (class "Default")
      (node (ref "ADC_DAC_EXT") (pin "3") (pinfunction "3_3") (pintype "passive"))
      (node (ref "PCF8591") (pin "1") (pinfunction "AIN0_1") (pintype "input"))
    )
    (net (code "9") (name "/ADC1_EXT") (class "Default")
      (node (ref "ADC_DAC_EXT") (pin "4") (pinfunction "4_4") (pintype "passive"))
      (node (ref "PCF8591") (pin "2") (pinfunction "AIN1_2") (pintype "input"))
      (node (ref "R19") (pin "1") (pinfunction "1_1") (pintype "passive"))
      (node (ref "SOIL_HUMIDITY_METER") (pin "2") (pinfunction "2_2") (pintype "passive"))
    )
    (net (code "10") (name "/ADC_ESP") (class "Default")
      (node (ref "ADC_DAC_EXT") (pin "2") (pinfunction "2_2") (pintype "passive"))
      (node (ref "ESP-07S") (pin "ADC") (pinfunction "ADC_ADC") (pintype "input"))
    )
    (net (code "11") (name "/ADC_LIGHT") (class "Default")
      (node (ref "ADC_LIGHT") (pin "P1") (pinfunction "1_P1") (pintype "passive"))
      (node (ref "PCF8591") (pin "3") (pinfunction "AIN2_3") (pintype "input"))
      (node (ref "R8") (pin "1") (pinfunction "1_1") (pintype "passive"))
    )
    (net (code "12") (name "/B_DWN") (class "Default")
      (node (ref "B_DWN") (pin "1") (pinfunction "1_1") (pintype "passive"))
      (node (ref "B_DWN") (pin "2") (pinfunction "2_2") (pintype "passive"))
      (node (ref "PCF8575") (pin "17") (pinfunction "P14_17") (pintype "bidirectional"))
      (node (ref "R34") (pin "1") (pinfunction "1_1") (pintype "passive"))
    )
    (net (code "13") (name "/B_LFT") (class "Default")
      (node (ref "B_LFT") (pin "1") (pinfunction "1_1") (pintype "passive"))
      (node (ref "B_LFT") (pin "2") (pinfunction "2_2") (pintype "passive"))
      (node (ref "PCF8575") (pin "14") (pinfunction "P11_14") (pintype "bidirectional"))
      (node (ref "R35") (pin "1") (pinfunction "1_1") (pintype "passive"))
    )
    (net (code "14") (name "/B_LPAG") (class "Default")
      (node (ref "B_LPAG") (pin "1") (pinfunction "1_1") (pintype "passive"))
      (node (ref "B_LPAG") (pin "2") (pinfunction "2_2") (pintype "passive"))
      (node (ref "PCF8575") (pin "18") (pinfunction "P15_18") (pintype "bidirectional"))
      (node (ref "R4") (pin "1") (pinfunction "1_1") (pintype "passive"))
    )
    (net (code "15") (name "/B_OK") (class "Default")
      (node (ref "B_OK") (pin "1") (pinfunction "1_1") (pintype "passive"))
      (node (ref "B_OK") (pin "2") (pinfunction "2_2") (pintype "passive"))
      (node (ref "PCF8575") (pin "13") (pinfunction "P10_13") (pintype "bidirectional"))
      (node (ref "R33") (pin "1") (pinfunction "1_1") (pintype "passive"))
    )
    (net (code "16") (name "/B_RGHT") (class "Default")
      (node (ref "B_RGHT") (pin "1") (pinfunction "1_1") (pintype "passive"))
      (node (ref "B_RGHT") (pin "2") (pinfunction "2_2") (pintype "passive"))
      (node (ref "PCF8575") (pin "15") (pinfunction "P12_15") (pintype "bidirectional"))
      (node (ref "R36") (pin "1") (pinfunction "1_1") (pintype "passive"))
    )
    (net (code "17") (name "/B_RPAG") (class "Default")
      (node (ref "B_RPAG") (pin "1") (pinfunction "1_1") (pintype "passive"))
      (node (ref "B_RPAG") (pin "2") (pinfunction "2_2") (pintype "passive"))
      (node (ref "PCF8575") (pin "19") (pinfunction "P16_19") (pintype "bidirectional"))
      (node (ref "R12") (pin "1") (pinfunction "1_1") (pintype "passive"))
    )
    (net (code "18") (name "/B_UP") (class "Default")
      (node (ref "B_UP") (pin "1") (pinfunction "1_1") (pintype "passive"))
      (node (ref "B_UP") (pin "2") (pinfunction "2_2") (pintype "passive"))
      (node (ref "PCF8575") (pin "16") (pinfunction "P13_16") (pintype "bidirectional"))
      (node (ref "R37") (pin "1") (pinfunction "1_1") (pintype "passive"))
    )
    (net (code "19") (name "/CURRENT_SENS") (class "Default")
      (node (ref "MAX471") (pin "8") (pinfunction "IOUT_8") (pintype "output"))
      (node (ref "PCF8591") (pin "4") (pinfunction "AIN3_4") (pintype "input"))
      (node (ref "R32") (pin "2") (pinfunction "2_2") (pintype "passive"))
    )
    (net (code "20") (name "/DAC") (class "Default")
      (node (ref "ADC_DAC_EXT") (pin "5") (pinfunction "5_5") (pintype "passive"))
      (node (ref "Q4") (pin "2") (pinfunction "SOURCE_2") (pintype "bidirectional"))
      (node (ref "Q5") (pin "3") (pinfunction "DRAIN_3") (pintype "bidirectional"))
      (node (ref "R47") (pin "2") (pinfunction "2_2") (pintype "passive"))
    )
    (net (code "21") (name "/FLASH") (class "Default")
      (node (ref "ESP-07S") (pin "GPIO0") (pinfunction "GPIO0~{}_GPIO0") (pintype "bidirectional"))
      (node (ref "FLASH") (pin "1") (pinfunction "1_1") (pintype "passive"))
      (node (ref "FLASH") (pin "2") (pinfunction "2_2") (pintype "passive"))
      (node (ref "JP_RS232") (pin "2") (pinfunction "2_2") (pintype "passive"))
      (node (ref "R21") (pin "1") (pinfunction "1_1") (pintype "passive"))
    )
    (net (code "22") (name "/INP_INT") (class "Default")
      (node (ref "ESP-07S") (pin "GPIO15") (pinfunction "GPIO15~{}_GPIO15") (pintype "bidirectional"))
      (node (ref "I2C_EXT") (pin "4") (pinfunction "4_4") (pintype "passive"))
      (node (ref "PCF8575") (pin "1") (pinfunction "INT_1") (pintype "bidirectional"))
      (node (ref "R22") (pin "2") (pinfunction "2_2") (pintype "passive"))
    )
    (net (code "23") (name "/IO0") (class "Default")
      (node (ref "JP1") (pin "5") (pinfunction "5_5") (pintype "passive"))
      (node (ref "PCF8575") (pin "4") (pinfunction "PO0_4") (pintype "bidirectional"))
    )
    (net (code "24") (name "/IO1") (class "Default")
      (node (ref "JP1") (pin "7") (pinfunction "7_7") (pintype "passive"))
      (node (ref "PCF8575") (pin "5") (pinfunction "PO1_5") (pintype "bidirectional"))
    )
    (net (code "25") (name "/IO2") (class "Default")
      (node (ref "JP1") (pin "9") (pinfunction "9_9") (pintype "passive"))
      (node (ref "PCF8575") (pin "6") (pinfunction "PO2_6") (pintype "bidirectional"))
    )
    (net (code "26") (name "/IO3") (class "Default")
      (node (ref "JP1") (pin "11") (pinfunction "11_11") (pintype "passive"))
      (node (ref "PCF8575") (pin "7") (pinfunction "PO3_7") (pintype "bidirectional"))
    )
    (net (code "27") (name "/IO4") (class "Default")
      (node (ref "JP1") (pin "13") (pinfunction "13_13") (pintype "passive"))
      (node (ref "PCF8575") (pin "8") (pinfunction "PO4_8") (pintype "bidirectional"))
    )
    (net (code "28") (name "/LED0") (class "Default")
      (node (ref "PCA9685") (pin "17") (pinfunction "PWM10_17") (pintype "output"))
      (node (ref "RQL1") (pin "1") (pinfunction "1_1") (pintype "passive"))
      (node (ref "U$13") (pin "3") (pinfunction "DIM_3") (pintype "bidirectional"))
    )
    (net (code "29") (name "/LED1") (class "Default")
      (node (ref "PCA9685") (pin "18") (pinfunction "PWM11_18") (pintype "output"))
      (node (ref "RQL2") (pin "1") (pinfunction "1_1") (pintype "passive"))
      (node (ref "U$6") (pin "3") (pinfunction "DIM_3") (pintype "bidirectional"))
    )
    (net (code "30") (name "/LED1O+") (class "Default")
      (node (ref "LED1") (pin "P2") (pinfunction "2_P2") (pintype "passive"))
      (node (ref "R26") (pin "2") (pinfunction "2_2") (pintype "passive"))
      (node (ref "R44") (pin "2") (pinfunction "2_2") (pintype "passive"))
      (node (ref "U$13") (pin "4") (pinfunction "CSN_4") (pintype "bidirectional"))
    )
    (net (code "31") (name "/LED1O-") (class "Default")
      (node (ref "L1") (pin "1") (pinfunction "1_1") (pintype "passive"))
      (node (ref "LED1") (pin "P1") (pinfunction "1_P1") (pintype "passive"))
    )
    (net (code "32") (name "/LED2") (class "Default")
      (node (ref "PCA9685") (pin "19") (pinfunction "PWM12_19") (pintype "output"))
      (node (ref "RQL3") (pin "1") (pinfunction "1_1") (pintype "passive"))
      (node (ref "U$7") (pin "3") (pinfunction "DIM_3") (pintype "bidirectional"))
    )
    (net (code "33") (name "/LED2O+") (class "Default")
      (node (ref "LED2") (pin "P2") (pinfunction "2_P2") (pintype "passive"))
      (node (ref "R27") (pin "2") (pinfunction "2_2") (pintype "passive"))
      (node (ref "R43") (pin "2") (pinfunction "2_2") (pintype "passive"))
      (node (ref "U$6") (pin "4") (pinfunction "CSN_4") (pintype "bidirectional"))
    )
    (net (code "34") (name "/LED2O-") (class "Default")
      (node (ref "L2") (pin "1") (pinfunction "1_1") (pintype "passive"))
      (node (ref "LED2") (pin "P1") (pinfunction "1_P1") (pintype "passive"))
    )
    (net (code "35") (name "/LED3") (class "Default")
      (node (ref "PCA9685") (pin "20") (pinfunction "PWM13_20") (pintype "output"))
      (node (ref "RQL4") (pin "1") (pinfunction "1_1") (pintype "passive"))
      (node (ref "U$8") (pin "3") (pinfunction "DIM_3") (pintype "bidirectional"))
    )
    (net (code "36") (name "/LED3O+") (class "Default")
      (node (ref "LED3") (pin "P2") (pinfunction "2_P2") (pintype "passive"))
      (node (ref "R28") (pin "2") (pinfunction "2_2") (pintype "passive"))
      (node (ref "R45") (pin "2") (pinfunction "2_2") (pintype "passive"))
      (node (ref "U$7") (pin "4") (pinfunction "CSN_4") (pintype "bidirectional"))
    )
    (net (code "37") (name "/LED3O-") (class "Default")
      (node (ref "L3") (pin "1") (pinfunction "1_1") (pintype "passive"))
      (node (ref "LED3") (pin "P1") (pinfunction "1_P1") (pintype "passive"))
    )
    (net (code "38") (name "/LED4") (class "Default")
      (node (ref "PCA9685") (pin "21") (pinfunction "PWM14_21") (pintype "output"))
      (node (ref "RQL5") (pin "1") (pinfunction "1_1") (pintype "passive"))
      (node (ref "U$9") (pin "3") (pinfunction "DIM_3") (pintype "bidirectional"))
    )
    (net (code "39") (name "/LED4O+") (class "Default")
      (node (ref "LED4") (pin "P2") (pinfunction "2_P2") (pintype "passive"))
      (node (ref "R29") (pin "2") (pinfunction "2_2") (pintype "passive"))
      (node (ref "R42") (pin "2") (pinfunction "2_2") (pintype "passive"))
      (node (ref "U$8") (pin "4") (pinfunction "CSN_4") (pintype "bidirectional"))
    )
    (net (code "40") (name "/LED4O-") (class "Default")
      (node (ref "L4") (pin "1") (pinfunction "1_1") (pintype "passive"))
      (node (ref "LED4") (pin "P1") (pinfunction "1_P1") (pintype "passive"))
    )
    (net (code "41") (name "/LED5") (class "Default")
      (node (ref "PCA9685") (pin "22") (pinfunction "PWM15_22") (pintype "output"))
      (node (ref "RQL6") (pin "1") (pinfunction "1_1") (pintype "passive"))
      (node (ref "U$10") (pin "3") (pinfunction "DIM_3") (pintype "bidirectional"))
    )
    (net (code "42") (name "/LED5O+") (class "Default")
      (node (ref "LED5") (pin "P2") (pinfunction "2_P2") (pintype "passive"))
      (node (ref "R30") (pin "2") (pinfunction "2_2") (pintype "passive"))
      (node (ref "R40") (pin "2") (pinfunction "2_2") (pintype "passive"))
      (node (ref "U$9") (pin "4") (pinfunction "CSN_4") (pintype "bidirectional"))
    )
    (net (code "43") (name "/LED5O-") (class "Default")
      (node (ref "L5") (pin "1") (pinfunction "1_1") (pintype "passive"))
      (node (ref "LED5") (pin "P1") (pinfunction "1_P1") (pintype "passive"))
    )
    (net (code "44") (name "/LED6O+") (class "Default")
      (node (ref "LED6") (pin "P2") (pinfunction "2_P2") (pintype "passive"))
      (node (ref "R31") (pin "2") (pinfunction "2_2") (pintype "passive"))
      (node (ref "R41") (pin "2") (pinfunction "2_2") (pintype "passive"))
      (node (ref "U$10") (pin "4") (pinfunction "CSN_4") (pintype "bidirectional"))
    )
    (net (code "45") (name "/LED6O-") (class "Default")
      (node (ref "L6") (pin "1") (pinfunction "1_1") (pintype "passive"))
      (node (ref "LED6") (pin "P1") (pinfunction "1_P1") (pintype "passive"))
    )
    (net (code "46") (name "/MISO") (class "Default")
      (node (ref "ESP-07S") (pin "GPIO12") (pinfunction "GPIO12~{}_GPIO12") (pintype "bidirectional"))
      (node (ref "JP_SPI_EXT") (pin "5") (pinfunction "5_5") (pintype "passive"))
    )
    (net (code "47") (name "/MOSI") (class "Default")
      (node (ref "ESP-07S") (pin "GPIO13") (pinfunction "GPIO13~{}_GPIO13") (pintype "bidirectional"))
      (node (ref "JP_SPI_EXT") (pin "6") (pinfunction "6_6") (pintype "passive"))
    )
    (net (code "48") (name "/OUT1") (class "Default")
      (node (ref "PCA9685") (pin "16") (pinfunction "PWM9_16") (pintype "output"))
      (node (ref "R7") (pin "1") (pinfunction "1_1") (pintype "passive"))
    )
    (net (code "49") (name "/OUT2") (class "Default")
      (node (ref "PCA9685") (pin "15") (pinfunction "PWM8_15") (pintype "output"))
      (node (ref "R5") (pin "1") (pinfunction "1_1") (pintype "passive"))
    )
    (net (code "50") (name "/OUT2+") (class "Default")
      (node (ref "D8") (pin "C") (pinfunction "C_C") (pintype "passive"))
      (node (ref "OUT2") (pin "P2") (pinfunction "2_P2") (pintype "passive"))
      (node (ref "OUT2_PWR") (pin "2") (pinfunction "2_2") (pintype "passive"))
    )
    (net (code "51") (name "/OUT3") (class "Default")
      (node (ref "PCA9685") (pin "13") (pinfunction "PWM7_13") (pintype "output"))
      (node (ref "R16") (pin "1") (pinfunction "1_1") (pintype "passive"))
    )
    (net (code "52") (name "/PWM0") (class "Default")
      (node (ref "JP1") (pin "6") (pinfunction "6_6") (pintype "passive"))
      (node (ref "PCA9685") (pin "6") (pinfunction "PWM0_6") (pintype "output"))
    )
    (net (code "53") (name "/PWM1") (class "Default")
      (node (ref "JP1") (pin "8") (pinfunction "8_8") (pintype "passive"))
      (node (ref "PCA9685") (pin "7") (pinfunction "PWM1_7") (pintype "output"))
    )
    (net (code "54") (name "/PWM2") (class "Default")
      (node (ref "JP1") (pin "10") (pinfunction "10_10") (pintype "passive"))
      (node (ref "PCA9685") (pin "8") (pinfunction "PWM2_8") (pintype "output"))
    )
    (net (code "55") (name "/PWM3") (class "Default")
      (node (ref "JP1") (pin "12") (pinfunction "12_12") (pintype "passive"))
      (node (ref "PCA9685") (pin "9") (pinfunction "PWM3_9") (pintype "output"))
    )
    (net (code "56") (name "/PWM4") (class "Default")
      (node (ref "JP1") (pin "14") (pinfunction "14_14") (pintype "passive"))
      (node (ref "PCA9685") (pin "10") (pinfunction "PWM4_10") (pintype "output"))
    )
    (net (code "57") (name "/RESET") (class "Default")
      (node (ref "B_RST") (pin "3") (pinfunction "3_3") (pintype "passive"))
      (node (ref "B_RST") (pin "4") (pinfunction "4_4") (pintype "passive"))
      (node (ref "ESP-07S") (pin "REST") (pinfunction "~{REST}_REST") (pintype "input"))
      (node (ref "R25") (pin "2") (pinfunction "2_2") (pintype "passive"))
    )
    (net (code "58") (name "/RXD") (class "Default")
      (node (ref "ESP-07S") (pin "RXD") (pinfunction "RXD_RXD") (pintype "input"))
      (node (ref "JP_RS232") (pin "4") (pinfunction "4_4") (pintype "passive"))
    )
    (net (code "59") (name "/SCK") (class "Default")
      (node (ref "ESP-07S") (pin "GPIO14") (pinfunction "GPIO14~{}_GPIO14") (pintype "bidirectional"))
      (node (ref "JP_SPI_EXT") (pin "3") (pinfunction "3_3") (pintype "passive"))
    )
    (net (code "60") (name "/SCL") (class "Default")
      (node (ref "ESP-07S") (pin "GPIO4") (pinfunction "GPIO5~{}_GPIO4") (pintype "bidirectional"))
      (node (ref "I2C_EXT") (pin "1") (pinfunction "1_1") (pintype "passive"))
      (node (ref "OLED_0.96_I2C") (pin "SCL") (pinfunction "SCL_SCL") (pintype "bidirectional"))
      (node (ref "PCA9685") (pin "26") (pinfunction "SCL_26") (pintype "bidirectional"))
      (node (ref "PCF8575") (pin "22") (pinfunction "SCL_22") (pintype "bidirectional"))
      (node (ref "PCF8591") (pin "10") (pinfunction "SCL_10") (pintype "input"))
      (node (ref "R23") (pin "1") (pinfunction "1_1") (pintype "passive"))
    )
    (net (code "61") (name "/SDA") (class "Default")
      (node (ref "ESP-07S") (pin "GPIO5") (pinfunction "GPIO4~{}_GPIO5") (pintype "bidirectional"))
      (node (ref "I2C_EXT") (pin "3") (pinfunction "3_3") (pintype "passive"))
      (node (ref "OLED_0.96_I2C") (pin "SDA") (pinfunction "SDA_SDA") (pintype "bidirectional"))
      (node (ref "PCA9685") (pin "27") (pinfunction "SDA_27") (pintype "bidirectional"))
      (node (ref "PCF8575") (pin "23") (pinfunction "SDA_23") (pintype "bidirectional"))
      (node (ref "PCF8591") (pin "9") (pinfunction "SDA_9") (pintype "bidirectional"))
      (node (ref "R24") (pin "1") (pinfunction "1_1") (pintype "passive"))
    )
    (net (code "62") (name "/SIGN1") (class "Default")
      (node (ref "LED_SIGN_1") (pin "C") (pinfunction "C_C") (pintype "passive"))
      (node (ref "PCA9685") (pin "12") (pinfunction "PWM6_12") (pintype "output"))
    )
    (net (code "63") (name "/SIGN2") (class "Default")
      (node (ref "LED_SIGN_2") (pin "C") (pinfunction "C_C") (pintype "passive"))
      (node (ref "PCA9685") (pin "11") (pinfunction "PWM5_11") (pintype "output"))
    )
    (net (code "64") (name "/SNS_LEVEL") (class "Default")
      (node (ref "LEVEL") (pin "P1") (pinfunction "1_P1") (pintype "passive"))
      (node (ref "PCF8575") (pin "20") (pinfunction "P17_20") (pintype "bidirectional"))
      (node (ref "R1") (pin "1") (pinfunction "1_1") (pintype "passive"))
    )
    (net (code "65") (name "/SPI_LATCH") (class "Default")
      (node (ref "ESP-07S") (pin "GPIO2") (pinfunction "GPIO2~{}_GPIO2") (pintype "bidirectional"))
      (node (ref "JP_SPI_EXT") (pin "7") (pinfunction "7_7") (pintype "passive"))
    )
    (net (code "66") (name "/TXD") (class "Default")
      (node (ref "ESP-07S") (pin "TXD") (pinfunction "TXD_TXD") (pintype "output"))
      (node (ref "JP_RS232") (pin "3") (pinfunction "3_3") (pintype "passive"))
    )
    (net (code "67") (name "/V_IN") (class "Default")
      (node (ref "CCL2") (pin "1") (pinfunction "1_1") (pintype "passive"))
      (node (ref "CCL4") (pin "1") (pinfunction "1_1") (pintype "passive"))
      (node (ref "CCL6") (pin "1") (pinfunction "1_1") (pintype "passive"))
      (node (ref "CL2") (pin "+") (pinfunction "+_+") (pintype "passive"))
      (node (ref "CL4") (pin "+") (pinfunction "+_+") (pintype "passive"))
      (node (ref "CL6") (pin "+") (pinfunction "+_+") (pintype "passive"))
      (node (ref "D3") (pin "C") (pinfunction "C_C") (pintype "passive"))
      (node (ref "D5") (pin "C") (pinfunction "C_C") (pintype "passive"))
      (node (ref "D7") (pin "C") (pinfunction "C_C") (pintype "passive"))
      (node (ref "JP1") (pin "2") (pinfunction "2_2") (pintype "passive"))
      (node (ref "MAX471") (pin "2") (pinfunction "BATT_2") (pintype "input"))
      (node (ref "MAX471") (pin "3") (pinfunction "RS+_3") (pintype "input"))
      (node (ref "OUT1_PWR") (pin "1") (pinfunction "1_1") (pintype "passive"))
      (node (ref "OUT2_PWR") (pin "1") (pinfunction "1_1") (pintype "passive"))
      (node (ref "PWR1") (pin "PWR") (pinfunction "PWR_PWR") (pintype "bidirectional"))
      (node (ref "PWR2") (pin "P2") (pinfunction "2_P2") (pintype "passive"))
      (node (ref "R17") (pin "2") (pinfunction "2_2") (pintype "passive"))
      (node (ref "R27") (pin "1") (pinfunction "1_1") (pintype "passive"))
      (node (ref "R29") (pin "1") (pinfunction "1_1") (pintype "passive"))
      (node (ref "R31") (pin "1") (pinfunction "1_1") (pintype "passive"))
      (node (ref "R41") (pin "1") (pinfunction "1_1") (pintype "passive"))
      (node (ref "R42") (pin "1") (pinfunction "1_1") (pintype "passive"))
      (node (ref "R43") (pin "1") (pinfunction "1_1") (pintype "passive"))
      (node (ref "U$10") (pin "5") (pinfunction "VIN_5") (pintype "bidirectional"))
      (node (ref "U$12") (pin "P$2") (pinfunction "V_IN_P$2") (pintype "bidirectional"))
      (node (ref "U$6") (pin "5") (pinfunction "VIN_5") (pintype "bidirectional"))
      (node (ref "U$8") (pin "5") (pinfunction "VIN_5") (pintype "bidirectional"))
    )
    (net (code "68") (name "/V_IN_CURR") (class "Default")
      (node (ref "CCL1") (pin "1") (pinfunction "1_1") (pintype "passive"))
      (node (ref "CCL3") (pin "1") (pinfunction "1_1") (pintype "passive"))
      (node (ref "CCL5") (pin "1") (pinfunction "1_1") (pintype "passive"))
      (node (ref "CL1") (pin "+") (pinfunction "+_+") (pintype "passive"))
      (node (ref "CL3") (pin "+") (pinfunction "+_+") (pintype "passive"))
      (node (ref "CL5") (pin "+") (pinfunction "+_+") (pintype "passive"))
      (node (ref "D2") (pin "C") (pinfunction "C_C") (pintype "passive"))
      (node (ref "D4") (pin "C") (pinfunction "C_C") (pintype "passive"))
      (node (ref "D6") (pin "C") (pinfunction "C_C") (pintype "passive"))
      (node (ref "MAX471") (pin "6") (pinfunction "RS-_6") (pintype "input"))
      (node (ref "MAX471") (pin "7") (pinfunction "LOAD_7") (pintype "output"))
      (node (ref "R17") (pin "1") (pinfunction "1_1") (pintype "passive"))
      (node (ref "R26") (pin "1") (pinfunction "1_1") (pintype "passive"))
      (node (ref "R28") (pin "1") (pinfunction "1_1") (pintype "passive"))
      (node (ref "R30") (pin "1") (pinfunction "1_1") (pintype "passive"))
      (node (ref "R40") (pin "1") (pinfunction "1_1") (pintype "passive"))
      (node (ref "R44") (pin "1") (pinfunction "1_1") (pintype "passive"))
      (node (ref "R45") (pin "1") (pinfunction "1_1") (pintype "passive"))
      (node (ref "U$13") (pin "5") (pinfunction "VIN_5") (pintype "bidirectional"))
      (node (ref "U$7") (pin "5") (pinfunction "VIN_5") (pintype "bidirectional"))
      (node (ref "U$9") (pin "5") (pinfunction "VIN_5") (pintype "bidirectional"))
    )
    (net (code "69") (name "GND") (class "Default")
      (node (ref "ADC_DAC_EXT") (pin "6") (pinfunction "6_6") (pintype "passive"))
      (node (ref "ADC_LIGHT") (pin "P2") (pinfunction "2_P2") (pintype "passive"))
      (node (ref "B_DWN") (pin "3") (pinfunction "3_3") (pintype "passive"))
      (node (ref "B_DWN") (pin "4") (pinfunction "4_4") (pintype "passive"))
      (node (ref "B_LFT") (pin "3") (pinfunction "3_3") (pintype "passive"))
      (node (ref "B_LFT") (pin "4") (pinfunction "4_4") (pintype "passive"))
      (node (ref "B_LPAG") (pin "3") (pinfunction "3_3") (pintype "passive"))
      (node (ref "B_LPAG") (pin "4") (pinfunction "4_4") (pintype "passive"))
      (node (ref "B_OK") (pin "3") (pinfunction "3_3") (pintype "passive"))
      (node (ref "B_OK") (pin "4") (pinfunction "4_4") (pintype "passive"))
      (node (ref "B_RGHT") (pin "3") (pinfunction "3_3") (pintype "passive"))
      (node (ref "B_RGHT") (pin "4") (pinfunction "4_4") (pintype "passive"))
      (node (ref "B_RPAG") (pin "3") (pinfunction "3_3") (pintype "passive"))
      (node (ref "B_RPAG") (pin "4") (pinfunction "4_4") (pintype "passive"))
      (node (ref "B_RST") (pin "1") (pinfunction "1_1") (pintype "passive"))
      (node (ref "B_RST") (pin "2") (pinfunction "2_2") (pintype "passive"))
      (node (ref "B_UP") (pin "3") (pinfunction "3_3") (pintype "passive"))
      (node (ref "B_UP") (pin "4") (pinfunction "4_4") (pintype "passive"))
      (node (ref "C1") (pin "-") (pinfunction "-_-") (pintype "passive"))
      (node (ref "C12") (pin "2") (pinfunction "2_2") (pintype "passive"))
      (node (ref "C3") (pin "-") (pinfunction "-_-") (pintype "passive"))
      (node (ref "CCL1") (pin "2") (pinfunction "2_2") (pintype "passive"))
      (node (ref "CCL2") (pin "2") (pinfunction "2_2") (pintype "passive"))
      (node (ref "CCL3") (pin "2") (pinfunction "2_2") (pintype "passive"))
      (node (ref "CCL4") (pin "2") (pinfunction "2_2") (pintype "passive"))
      (node (ref "CCL5") (pin "2") (pinfunction "2_2") (pintype "passive"))
      (node (ref "CCL6") (pin "2") (pinfunction "2_2") (pintype "passive"))
      (node (ref "CL1") (pin "-") (pinfunction "-_-") (pintype "passive"))
      (node (ref "CL2") (pin "-") (pinfunction "-_-") (pintype "passive"))
      (node (ref "CL3") (pin "-") (pinfunction "-_-") (pintype "passive"))
      (node (ref "CL4") (pin "-") (pinfunction "-_-") (pintype "passive"))
      (node (ref "CL5") (pin "-") (pinfunction "-_-") (pintype "passive"))
      (node (ref "CL6") (pin "-") (pinfunction "-_-") (pintype "passive"))
      (node (ref "D9") (pin "A") (pinfunction "A_A") (pintype "passive"))
      (node (ref "ESP-07S") (pin "GND") (pinfunction "GND_GND") (pintype "power_in"))
      (node (ref "FLASH") (pin "3") (pinfunction "3_3") (pintype "passive"))
      (node (ref "FLASH") (pin "4") (pinfunction "4_4") (pintype "passive"))
      (node (ref "I2C_EXT") (pin "6") (pinfunction "6_6") (pintype "passive"))
      (node (ref "JMP_GND") (pin "2") (pinfunction "2_2") (pintype "passive"))
      (node (ref "JP1") (pin "4") (pinfunction "4_4") (pintype "passive"))
      (node (ref "JP_RS232") (pin "5") (pinfunction "5_5") (pintype "passive"))
      (node (ref "JP_SPI_EXT") (pin "2") (pinfunction "2_2") (pintype "passive"))
      (node (ref "LEVEL") (pin "P2") (pinfunction "2_P2") (pintype "passive"))
      (node (ref "LM1117-3.3") (pin "1") (pinfunction "GND_1") (pintype "power_in"))
      (node (ref "MAX471") (pin "1") (pinfunction "SHDN_1") (pintype "input"))
      (node (ref "MAX471") (pin "4") (pinfunction "GND_4") (pintype "power_in"))
      (node (ref "OUT3") (pin "P1") (pinfunction "1_P1") (pintype "passive"))
      (node (ref "PCA9685") (pin "1") (pinfunction "A0_1") (pintype "bidirectional"))
      (node (ref "PCA9685") (pin "14") (pinfunction "GND_14") (pintype "power_in"))
      (node (ref "PCA9685") (pin "2") (pinfunction "A1_2") (pintype "bidirectional"))
      (node (ref "PCA9685") (pin "24") (pinfunction "A5_24") (pintype "bidirectional"))
      (node (ref "PCA9685") (pin "25") (pinfunction "EXTCLK_25") (pintype "input"))
      (node (ref "PCA9685") (pin "3") (pinfunction "A2_3") (pintype "bidirectional"))
      (node (ref "PCA9685") (pin "4") (pinfunction "A3_4") (pintype "bidirectional"))
      (node (ref "PCA9685") (pin "5") (pinfunction "A4_5") (pintype "bidirectional"))
      (node (ref "PCF8575") (pin "12") (pinfunction "GND_12") (pintype "bidirectional"))
      (node (ref "PCF8575") (pin "2") (pinfunction "A1_2") (pintype "bidirectional"))
      (node (ref "PCF8575") (pin "21") (pinfunction "A0_21") (pintype "bidirectional"))
      (node (ref "PCF8575") (pin "3") (pinfunction "A2_3") (pintype "bidirectional"))
      (node (ref "PCF8591") (pin "12") (pinfunction "EXT_12") (pintype "input"))
      (node (ref "PCF8591") (pin "13") (pinfunction "AGND_13") (pintype "power_in"))
      (node (ref "PCF8591") (pin "5") (pinfunction "A0_5") (pintype "input"))
      (node (ref "PCF8591") (pin "6") (pinfunction "A1_6") (pintype "input"))
      (node (ref "PCF8591") (pin "7") (pinfunction "A2_7") (pintype "input"))
      (node (ref "PCF8591") (pin "8") (pinfunction "VSS_8") (pintype "power_in"))
      (node (ref "PWR1") (pin "GND") (pinfunction "GND_GND") (pintype "bidirectional"))
      (node (ref "PWR1") (pin "GNDBREAK") (pinfunction "GNDBREAK_GNDBREAK") (pintype "bidirectional"))
      (node (ref "PWR2") (pin "P1") (pinfunction "1_P1") (pintype "passive"))
      (node (ref "Q5") (pin "1") (pinfunction "GATE_1") (pintype "bidirectional"))
      (node (ref "Q5") (pin "2") (pinfunction "SOURCE_2") (pintype "bidirectional"))
      (node (ref "QO3-N") (pin "2") (pinfunction "SOURCE_2") (pintype "bidirectional"))
      (node (ref "Q_OUT1") (pin "3") (pinfunction "SOURCE_3") (pintype "bidirectional"))
      (node (ref "Q_OUT2") (pin "3") (pinfunction "SOURCE_3") (pintype "bidirectional"))
      (node (ref "Q_OUT2SM") (pin "2") (pinfunction "SOURCE_2") (pintype "bidirectional"))
      (node (ref "R18") (pin "1") (pinfunction "1_1") (pintype "passive"))
      (node (ref "R22") (pin "1") (pinfunction "1_1") (pintype "passive"))
      (node (ref "R32") (pin "1") (pinfunction "1_1") (pintype "passive"))
      (node (ref "R47") (pin "1") (pinfunction "1_1") (pintype "passive"))
      (node (ref "SOIL_HUMIDITY_METER") (pin "3") (pinfunction "3_3") (pintype "passive"))
      (node (ref "U$10") (pin "2") (pinfunction "GND_2") (pintype "bidirectional"))
      (node (ref "U$10") (pin "PAD") (pinfunction "PAD_PAD") (pintype "bidirectional"))
      (node (ref "U$12") (pin "P$1") (pinfunction "GNDI_P$1") (pintype "bidirectional"))
      (node (ref "U$12") (pin "P$3") (pinfunction "GNDO_P$3") (pintype "bidirectional"))
      (node (ref "U$13") (pin "2") (pinfunction "GND_2") (pintype "bidirectional"))
      (node (ref "U$13") (pin "PAD") (pinfunction "PAD_PAD") (pintype "bidirectional"))
      (node (ref "U$6") (pin "2") (pinfunction "GND_2") (pintype "bidirectional"))
      (node (ref "U$6") (pin "PAD") (pinfunction "PAD_PAD") (pintype "bidirectional"))
      (node (ref "U$7") (pin "2") (pinfunction "GND_2") (pintype "bidirectional"))
      (node (ref "U$7") (pin "PAD") (pinfunction "PAD_PAD") (pintype "bidirectional"))
      (node (ref "U$8") (pin "2") (pinfunction "GND_2") (pintype "bidirectional"))
      (node (ref "U$8") (pin "PAD") (pinfunction "PAD_PAD") (pintype "bidirectional"))
      (node (ref "U$9") (pin "2") (pinfunction "GND_2") (pintype "bidirectional"))
      (node (ref "U$9") (pin "PAD") (pinfunction "PAD_PAD") (pintype "bidirectional"))
    )
    (net (code "70") (name "Net-(AC1_CTL-2)") (class "Default")
      (node (ref "AC1_CTL") (pin "P2") (pinfunction "2_P2") (pintype "passive"))
      (node (ref "OK1") (pin "2") (pinfunction "C_2") (pintype "passive"))
    )
    (net (code "71") (name "Net-(AC2_CTL-1)") (class "Default")
      (node (ref "AC2_CTL") (pin "P1") (pinfunction "1_P1") (pintype "passive"))
      (node (ref "OK2") (pin "2") (pinfunction "C_2") (pintype "passive"))
    )
    (net (code "72") (name "Net-(AC3_CTL-2)") (class "Default")
      (node (ref "AC3_CTL") (pin "P2") (pinfunction "2_P2") (pintype "passive"))
      (node (ref "OK3") (pin "2") (pinfunction "C_2") (pintype "passive"))
    )
    (net (code "73") (name "Net-(AC11-1)") (class "Default")
      (node (ref "AC11") (pin "P1") (pinfunction "1_P1") (pintype "passive"))
      (node (ref "R9") (pin "1") (pinfunction "1_1") (pintype "passive"))
      (node (ref "T1") (pin "T2") (pinfunction "A2_T2") (pintype "passive"))
    )
    (net (code "74") (name "Net-(AC11-2)") (class "Default")
      (node (ref "AC11") (pin "P2") (pinfunction "2_P2") (pintype "passive"))
      (node (ref "AC12") (pin "P1") (pinfunction "1_P1") (pintype "passive"))
    )
    (net (code "75") (name "Net-(AC12-2)") (class "Default")
      (node (ref "AC12") (pin "P2") (pinfunction "2_P2") (pintype "passive"))
      (node (ref "T1") (pin "T1") (pinfunction "A1_T1") (pintype "passive"))
    )
    (net (code "76") (name "Net-(AC21-1)") (class "Default")
      (node (ref "AC21") (pin "P1") (pinfunction "1_P1") (pintype "passive"))
      (node (ref "R10") (pin "1") (pinfunction "1_1") (pintype "passive"))
      (node (ref "T2") (pin "T2") (pinfunction "A2_T2") (pintype "passive"))
    )
    (net (code "77") (name "Net-(AC21-2)") (class "Default")
      (node (ref "AC21") (pin "P2") (pinfunction "2_P2") (pintype "passive"))
      (node (ref "AC22") (pin "P1") (pinfunction "1_P1") (pintype "passive"))
    )
    (net (code "78") (name "Net-(AC22-2)") (class "Default")
      (node (ref "AC22") (pin "P2") (pinfunction "2_P2") (pintype "passive"))
      (node (ref "T2") (pin "T1") (pinfunction "A1_T1") (pintype "passive"))
    )
    (net (code "79") (name "Net-(AC31-1)") (class "Default")
      (node (ref "AC31") (pin "P1") (pinfunction "1_P1") (pintype "passive"))
      (node (ref "R13") (pin "1") (pinfunction "1_1") (pintype "passive"))
      (node (ref "T3") (pin "T2") (pinfunction "A2_T2") (pintype "passive"))
    )
    (net (code "80") (name "Net-(AC31-2)") (class "Default")
      (node (ref "AC31") (pin "P2") (pinfunction "2_P2") (pintype "passive"))
      (node (ref "AC32") (pin "P1") (pinfunction "1_P1") (pintype "passive"))
    )
    (net (code "81") (name "Net-(AC32-2)") (class "Default")
      (node (ref "AC32") (pin "P2") (pinfunction "2_P2") (pintype "passive"))
      (node (ref "T3") (pin "T1") (pinfunction "A1_T1") (pintype "passive"))
    )
    (net (code "82") (name "Net-(ESP-07S-PadCH_PD)") (class "Default")
      (node (ref "ESP-07S") (pin "CH_PD") (pinfunction "CH_PD_CH_PD") (pintype "input"))
      (node (ref "R20") (pin "2") (pinfunction "2_2") (pintype "passive"))
    )
    (net (code "83") (name "Net-(JMP_GND-Pad1)") (class "Default")
      (node (ref "JMP_GND") (pin "1") (pinfunction "1_1") (pintype "passive"))
      (node (ref "JMP_VCC") (pin "3") (pinfunction "3_3") (pintype "passive"))
      (node (ref "OLED_0.96_I2C") (pin "VCC") (pinfunction "VCC_VCC") (pintype "bidirectional"))
    )
    (net (code "84") (name "Net-(JMP_GND-Pad3)") (class "Default")
      (node (ref "JMP_GND") (pin "3") (pinfunction "3_3") (pintype "passive"))
      (node (ref "JMP_VCC") (pin "1") (pinfunction "1_1") (pintype "passive"))
      (node (ref "OLED_0.96_I2C") (pin "GND") (pinfunction "GND_GND") (pintype "bidirectional"))
    )
    (net (code "85") (name "Net-(LED_SIGN_1-PadA)") (class "Default")
      (node (ref "LED_SIGN_1") (pin "A") (pinfunction "A_A") (pintype "passive"))
      (node (ref "R48") (pin "1") (pinfunction "1_1") (pintype "passive"))
    )
    (net (code "86") (name "Net-(LED_SIGN_2-PadA)") (class "Default")
      (node (ref "LED_SIGN_2") (pin "A") (pinfunction "A_A") (pintype "passive"))
      (node (ref "R49") (pin "1") (pinfunction "1_1") (pintype "passive"))
    )
    (net (code "87") (name "Net-(OK1-A)") (class "Default")
      (node (ref "OK1") (pin "1") (pinfunction "A_1") (pintype "passive"))
      (node (ref "R2") (pin "2") (pinfunction "2_2") (pintype "passive"))
    )
    (net (code "88") (name "Net-(OK1-A1)") (class "Default")
      (node (ref "OK1") (pin "4") (pinfunction "A1_4") (pintype "passive"))
      (node (ref "T1") (pin "G") (pinfunction "G_G") (pintype "passive"))
    )
    (net (code "89") (name "Net-(OK1-A2)") (class "Default")
      (node (ref "OK1") (pin "6") (pinfunction "A2_6") (pintype "passive"))
      (node (ref "R9") (pin "2") (pinfunction "2_2") (pintype "passive"))
    )
    (net (code "90") (name "Net-(OK2-A)") (class "Default")
      (node (ref "OK2") (pin "1") (pinfunction "A_1") (pintype "passive"))
      (node (ref "R3") (pin "2") (pinfunction "2_2") (pintype "passive"))
    )
    (net (code "91") (name "Net-(OK2-A1)") (class "Default")
      (node (ref "OK2") (pin "4") (pinfunction "A1_4") (pintype "passive"))
      (node (ref "T2") (pin "G") (pinfunction "G_G") (pintype "passive"))
    )
    (net (code "92") (name "Net-(OK2-A2)") (class "Default")
      (node (ref "OK2") (pin "6") (pinfunction "A2_6") (pintype "passive"))
      (node (ref "R10") (pin "2") (pinfunction "2_2") (pintype "passive"))
    )
    (net (code "93") (name "Net-(OK3-A)") (class "Default")
      (node (ref "OK3") (pin "1") (pinfunction "A_1") (pintype "passive"))
      (node (ref "R14") (pin "2") (pinfunction "2_2") (pintype "passive"))
    )
    (net (code "94") (name "Net-(OK3-A1)") (class "Default")
      (node (ref "OK3") (pin "4") (pinfunction "A1_4") (pintype "passive"))
      (node (ref "T3") (pin "G") (pinfunction "G_G") (pintype "passive"))
    )
    (net (code "95") (name "Net-(OK3-A2)") (class "Default")
      (node (ref "OK3") (pin "6") (pinfunction "A2_6") (pintype "passive"))
      (node (ref "R13") (pin "2") (pinfunction "2_2") (pintype "passive"))
    )
    (net (code "96") (name "Net-(OUT1-1)") (class "Default")
      (node (ref "D1") (pin "A") (pinfunction "A_A") (pintype "passive"))
      (node (ref "OUT1") (pin "P1") (pinfunction "1_P1") (pintype "passive"))
      (node (ref "Q_OUT1") (pin "2") (pinfunction "DRAIN_2") (pintype "bidirectional"))
    )
    (net (code "97") (name "Net-(OUT1-2)") (class "Default")
      (node (ref "D1") (pin "C") (pinfunction "C_C") (pintype "passive"))
      (node (ref "OUT1") (pin "P2") (pinfunction "2_P2") (pintype "passive"))
      (node (ref "OUT1_PWR") (pin "2") (pinfunction "2_2") (pintype "passive"))
    )
    (net (code "98") (name "Net-(OUT2-1)") (class "Default")
      (node (ref "D8") (pin "A") (pinfunction "A_A") (pintype "passive"))
      (node (ref "OUT2") (pin "P1") (pinfunction "1_P1") (pintype "passive"))
      (node (ref "Q_OUT2") (pin "2") (pinfunction "DRAIN_2") (pintype "bidirectional"))
      (node (ref "Q_OUT2SM") (pin "3") (pinfunction "DRAIN_3") (pintype "bidirectional"))
    )
    (net (code "99") (name "Net-(OUT3-2)") (class "Default")
      (node (ref "D9") (pin "C") (pinfunction "C_C") (pintype "passive"))
      (node (ref "OUT3") (pin "P2") (pinfunction "2_P2") (pintype "passive"))
      (node (ref "QO3-N") (pin "3") (pinfunction "DRAIN_3") (pintype "bidirectional"))
      (node (ref "QO3-P") (pin "3") (pinfunction "D_3") (pintype "passive"))
    )
    (net (code "100") (name "Net-(PCA9685-#OE)") (class "Default")
      (node (ref "PCA9685") (pin "23") (pinfunction "#OE_23") (pintype "input"))
      (node (ref "R18") (pin "2") (pinfunction "2_2") (pintype "passive"))
    )
    (net (code "101") (name "Net-(PCF8591-AOUT)") (class "Default")
      (node (ref "PCF8591") (pin "15") (pinfunction "AOUT_15") (pintype "output"))
      (node (ref "R46") (pin "1") (pinfunction "1_1") (pintype "passive"))
    )
    (net (code "102") (name "Net-(Q4-GATE)") (class "Default")
      (node (ref "Q4") (pin "1") (pinfunction "GATE_1") (pintype "bidirectional"))
      (node (ref "R46") (pin "2") (pinfunction "2_2") (pintype "passive"))
    )
    (net (code "103") (name "Net-(QO3-N-GATE)") (class "Default")
      (node (ref "QO3-N") (pin "1") (pinfunction "GATE_1") (pintype "bidirectional"))
      (node (ref "QO3-P") (pin "1") (pinfunction "G_1") (pintype "passive"))
      (node (ref "R15") (pin "1") (pinfunction "1_1") (pintype "passive"))
      (node (ref "R16") (pin "2") (pinfunction "2_2") (pintype "passive"))
    )
    (net (code "104") (name "Net-(Q_OUT1-GATE)") (class "Default")
      (node (ref "Q_OUT1") (pin "1") (pinfunction "GATE_1") (pintype "bidirectional"))
      (node (ref "R6") (pin "2") (pinfunction "2_2") (pintype "passive"))
      (node (ref "R7") (pin "2") (pinfunction "2_2") (pintype "passive"))
    )
    (net (code "105") (name "Net-(Q_OUT2-GATE)") (class "Default")
      (node (ref "Q_OUT2") (pin "1") (pinfunction "GATE_1") (pintype "bidirectional"))
      (node (ref "Q_OUT2SM") (pin "1") (pinfunction "GATE_1") (pintype "bidirectional"))
      (node (ref "R11") (pin "2") (pinfunction "2_2") (pintype "passive"))
      (node (ref "R5") (pin "2") (pinfunction "2_2") (pintype "passive"))
    )
    (net (code "106") (name "Net-(U$6-SW)") (class "Default")
      (node (ref "D3") (pin "A") (pinfunction "A_A") (pintype "passive"))
      (node (ref "L2") (pin "2") (pinfunction "2_2") (pintype "passive"))
      (node (ref "U$6") (pin "1") (pinfunction "SW_1") (pintype "bidirectional"))
    )
    (net (code "107") (name "Net-(U$7-SW)") (class "Default")
      (node (ref "D4") (pin "A") (pinfunction "A_A") (pintype "passive"))
      (node (ref "L3") (pin "2") (pinfunction "2_2") (pintype "passive"))
      (node (ref "U$7") (pin "1") (pinfunction "SW_1") (pintype "bidirectional"))
    )
    (net (code "108") (name "Net-(U$8-SW)") (class "Default")
      (node (ref "D5") (pin "A") (pinfunction "A_A") (pintype "passive"))
      (node (ref "L4") (pin "2") (pinfunction "2_2") (pintype "passive"))
      (node (ref "U$8") (pin "1") (pinfunction "SW_1") (pintype "bidirectional"))
    )
    (net (code "109") (name "Net-(U$9-SW)") (class "Default")
      (node (ref "D6") (pin "A") (pinfunction "A_A") (pintype "passive"))
      (node (ref "L5") (pin "2") (pinfunction "2_2") (pintype "passive"))
      (node (ref "U$9") (pin "1") (pinfunction "SW_1") (pintype "bidirectional"))
    )
    (net (code "110") (name "Net-(U$10-SW)") (class "Default")
      (node (ref "D7") (pin "A") (pinfunction "A_A") (pintype "passive"))
      (node (ref "L6") (pin "2") (pinfunction "2_2") (pintype "passive"))
      (node (ref "U$10") (pin "1") (pinfunction "SW_1") (pintype "bidirectional"))
    )
    (net (code "111") (name "Net-(U$13-SW)") (class "Default")
      (node (ref "D2") (pin "A") (pinfunction "A_A") (pintype "passive"))
      (node (ref "L1") (pin "2") (pinfunction "2_2") (pintype "passive"))
      (node (ref "U$13") (pin "1") (pinfunction "SW_1") (pintype "bidirectional"))
    )
    (net (code "112") (name "VDD") (class "Default")
      (node (ref "AC_KEYS") (pin "2") (pinfunction "2_2") (pintype "passive"))
      (node (ref "AC_KEYS") (pin "4") (pinfunction "4_4") (pintype "passive"))
      (node (ref "AC_KEYS") (pin "6") (pinfunction "6_6") (pintype "passive"))
      (node (ref "ADC_DAC_EXT") (pin "1") (pinfunction "1_1") (pintype "passive"))
      (node (ref "C1") (pin "+") (pinfunction "+_+") (pintype "passive"))
      (node (ref "C12") (pin "1") (pinfunction "1_1") (pintype "passive"))
      (node (ref "C3") (pin "+") (pinfunction "+_+") (pintype "passive"))
      (node (ref "ESP-07S") (pin "VCC") (pinfunction "VCC_VCC") (pintype "power_in"))
      (node (ref "I2C_EXT") (pin "2") (pinfunction "2_2") (pintype "passive"))
      (node (ref "JMP_VCC") (pin "2") (pinfunction "2_2") (pintype "passive"))
      (node (ref "JP1") (pin "3") (pinfunction "3_3") (pintype "passive"))
      (node (ref "JP_RS232") (pin "1") (pinfunction "1_1") (pintype "passive"))
      (node (ref "JP_SPI_EXT") (pin "1") (pinfunction "1_1") (pintype "passive"))
      (node (ref "LM1117-3.3") (pin "2") (pinfunction "OUT_2") (pintype "power_in"))
      (node (ref "LM1117-3.3") (pin "4") (pinfunction "MASS_4") (pintype "passive"))
      (node (ref "PCA9685") (pin "28") (pinfunction "VDD_28") (pintype "power_in"))
      (node (ref "PCF8575") (pin "24") (pinfunction "VCC_24") (pintype "bidirectional"))
      (node (ref "PCF8591") (pin "14") (pinfunction "VREF_14") (pintype "input"))
      (node (ref "PCF8591") (pin "16") (pinfunction "VDD_16") (pintype "power_in"))
      (node (ref "Q4") (pin "3") (pinfunction "DRAIN_3") (pintype "bidirectional"))
      (node (ref "R1") (pin "2") (pinfunction "2_2") (pintype "passive"))
      (node (ref "R11") (pin "1") (pinfunction "1_1") (pintype "passive"))
      (node (ref "R12") (pin "2") (pinfunction "2_2") (pintype "passive"))
      (node (ref "R19") (pin "2") (pinfunction "2_2") (pintype "passive"))
      (node (ref "R20") (pin "1") (pinfunction "1_1") (pintype "passive"))
      (node (ref "R21") (pin "2") (pinfunction "2_2") (pintype "passive"))
      (node (ref "R23") (pin "2") (pinfunction "2_2") (pintype "passive"))
      (node (ref "R24") (pin "2") (pinfunction "2_2") (pintype "passive"))
      (node (ref "R25") (pin "1") (pinfunction "1_1") (pintype "passive"))
      (node (ref "R33") (pin "2") (pinfunction "2_2") (pintype "passive"))
      (node (ref "R34") (pin "2") (pinfunction "2_2") (pintype "passive"))
      (node (ref "R35") (pin "2") (pinfunction "2_2") (pintype "passive"))
      (node (ref "R36") (pin "2") (pinfunction "2_2") (pintype "passive"))
      (node (ref "R37") (pin "2") (pinfunction "2_2") (pintype "passive"))
      (node (ref "R4") (pin "2") (pinfunction "2_2") (pintype "passive"))
      (node (ref "R48") (pin "2") (pinfunction "2_2") (pintype "passive"))
      (node (ref "R49") (pin "2") (pinfunction "2_2") (pintype "passive"))
      (node (ref "R6") (pin "1") (pinfunction "1_1") (pintype "passive"))
      (node (ref "R8") (pin "2") (pinfunction "2_2") (pintype "passive"))
      (node (ref "RQL1") (pin "2") (pinfunction "2_2") (pintype "passive"))
      (node (ref "RQL2") (pin "2") (pinfunction "2_2") (pintype "passive"))
      (node (ref "RQL3") (pin "2") (pinfunction "2_2") (pintype "passive"))
      (node (ref "RQL4") (pin "2") (pinfunction "2_2") (pintype "passive"))
      (node (ref "RQL5") (pin "2") (pinfunction "2_2") (pintype "passive"))
      (node (ref "RQL6") (pin "2") (pinfunction "2_2") (pintype "passive"))
      (node (ref "SOIL_HUMIDITY_METER") (pin "1") (pinfunction "1_1") (pintype "passive"))
    )
    (net (code "113") (name "unconnected-(ESP-07S-PadGPIO16)") (class "Default")
      (node (ref "ESP-07S") (pin "GPIO16") (pinfunction "GPIO16_GPIO16") (pintype "bidirectional"))
    )
    (net (code "114") (name "unconnected-(I2C_EXT-Pad5)") (class "Default")
      (node (ref "I2C_EXT") (pin "5") (pinfunction "5_5") (pintype "passive"))
    )
    (net (code "115") (name "unconnected-(JP1-Pad15)") (class "Default")
      (node (ref "JP1") (pin "15") (pinfunction "15_15") (pintype "passive"))
    )
    (net (code "116") (name "unconnected-(JP1-Pad16)") (class "Default")
      (node (ref "JP1") (pin "16") (pinfunction "16_16") (pintype "passive"))
    )
    (net (code "117") (name "unconnected-(JP_RS232-Pad6)") (class "Default")
      (node (ref "JP_RS232") (pin "6") (pinfunction "6_6") (pintype "passive"))
    )
    (net (code "118") (name "unconnected-(JP_SPI_EXT-Pad4)") (class "Default")
      (node (ref "JP_SPI_EXT") (pin "4") (pinfunction "4_4") (pintype "passive"))
    )
    (net (code "119") (name "unconnected-(JP_SPI_EXT-Pad8)") (class "Default")
      (node (ref "JP_SPI_EXT") (pin "8") (pinfunction "8_8") (pintype "passive"))
    )
    (net (code "120") (name "unconnected-(MAX471-SIGN-Pad5)") (class "Default")
      (node (ref "MAX471") (pin "5") (pinfunction "SIGN_5") (pintype "open_collector"))
    )
    (net (code "121") (name "unconnected-(PCF8591-OSC-Pad11)") (class "Default")
      (node (ref "PCF8591") (pin "11") (pinfunction "OSC_11") (pintype "input"))
    )
  )
)
